# IGresupply.net
KiCad netlist of a schematic drawn in Altium Designer
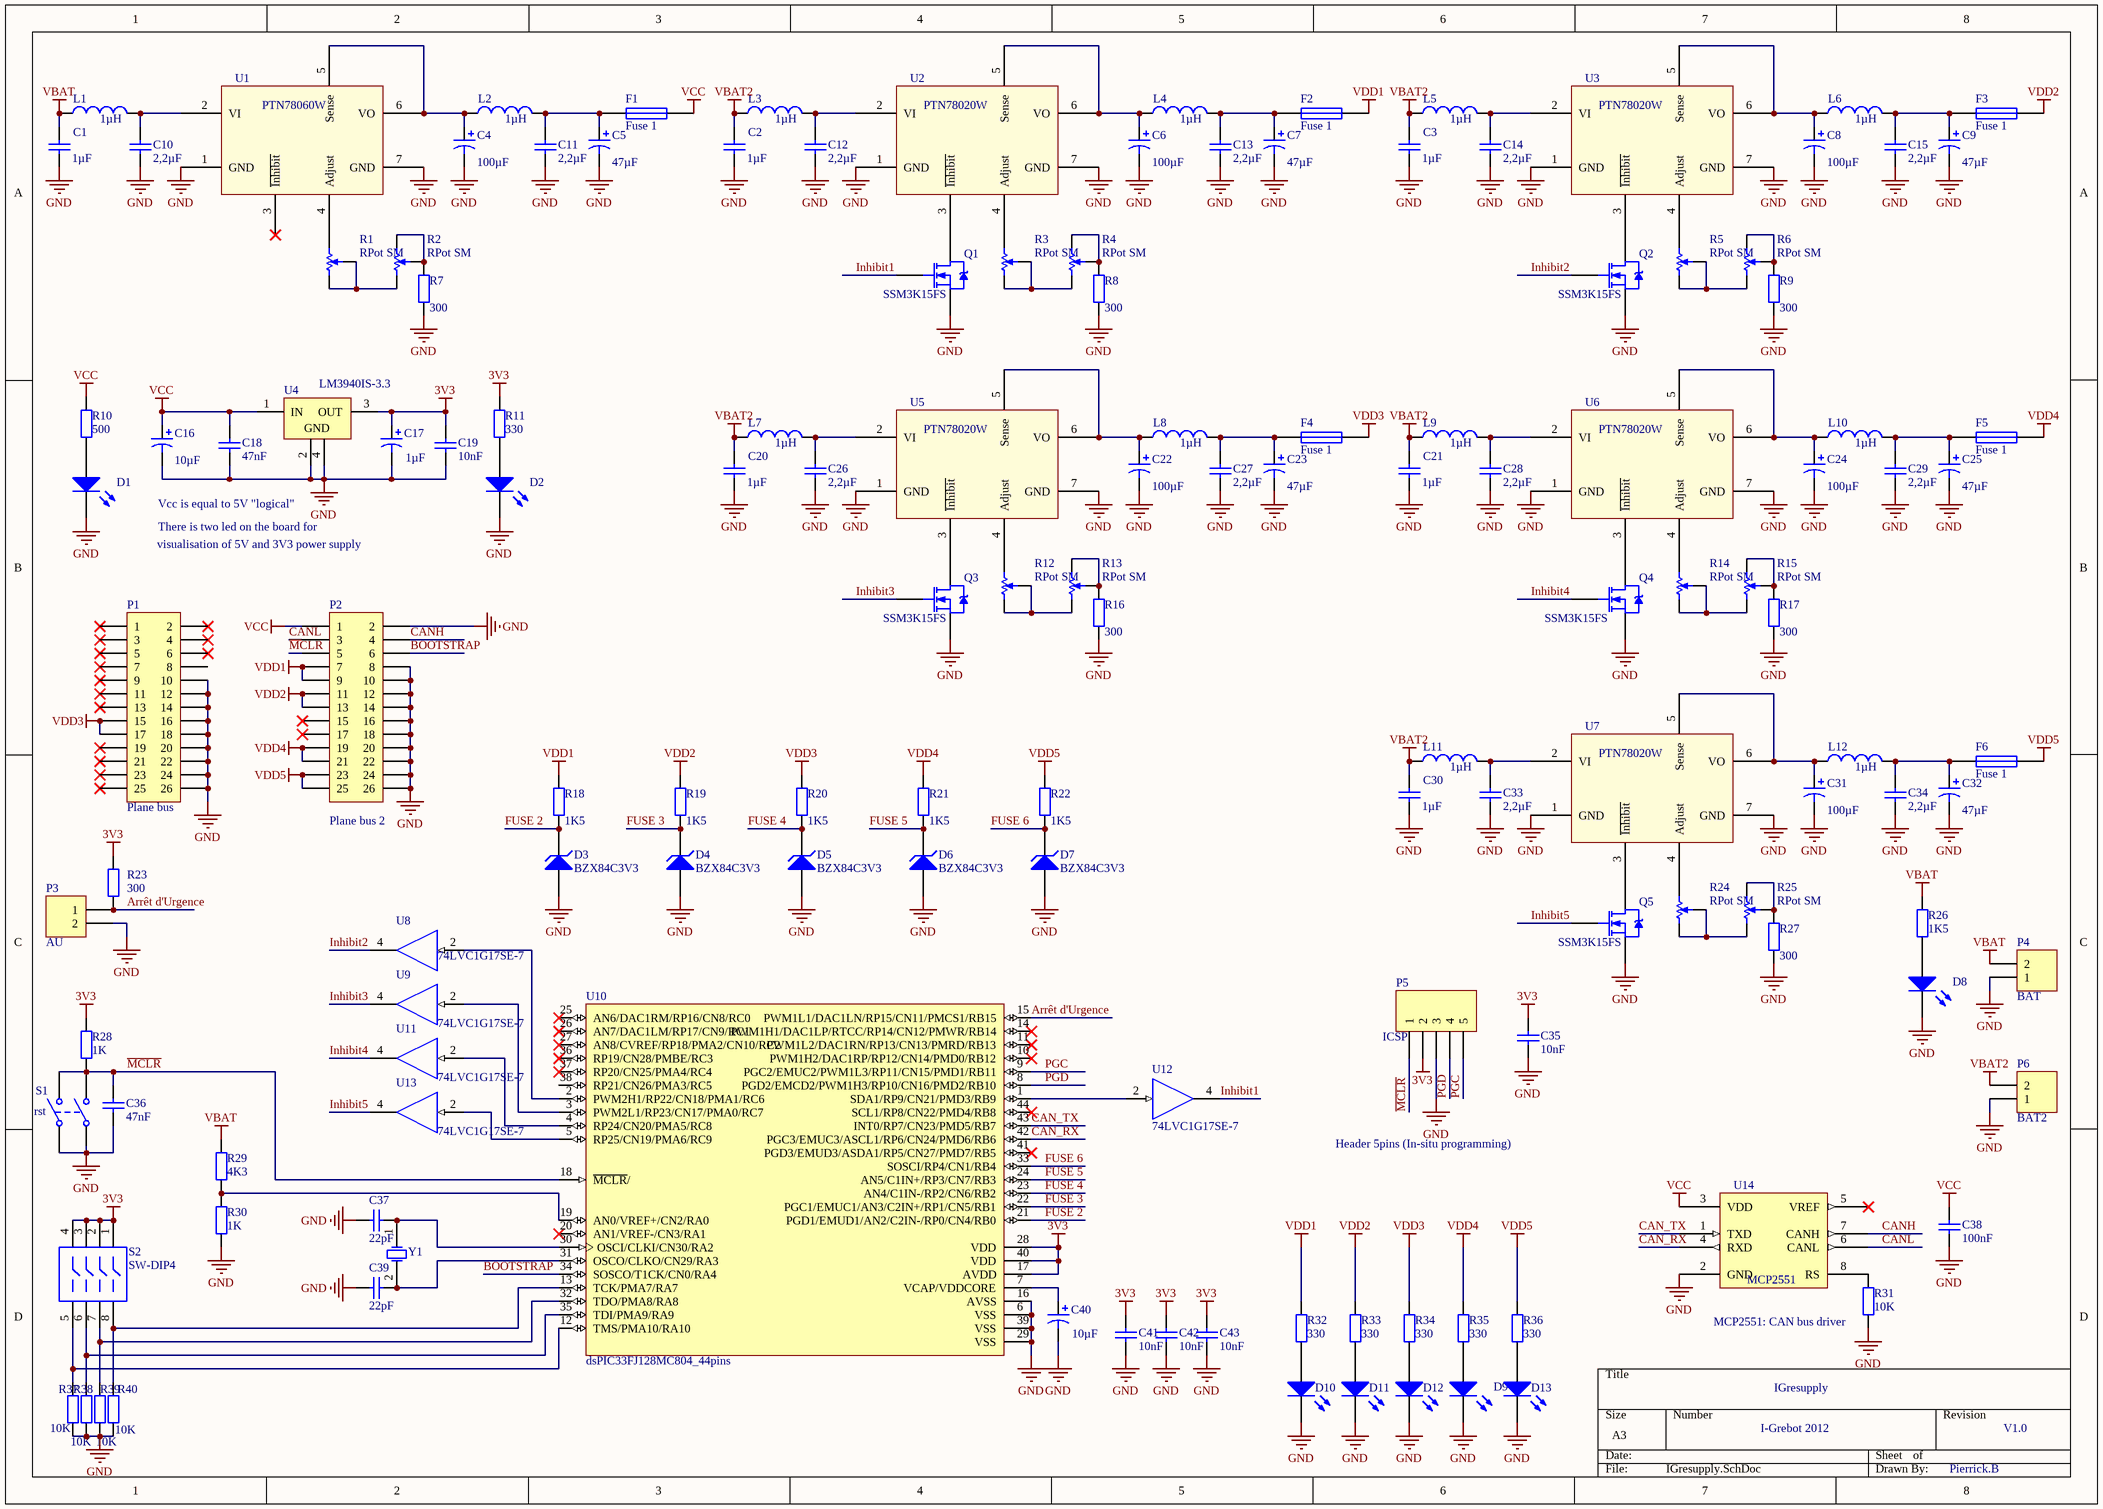
[diagram p0: IGresupply.SchDoc]

(export (version "E")
  (design (tool "Eeschema 10.0.6"))
  (components
    (comp (ref "C1")
      (value "1µF")
      (footprint "Boitier tantale A")
      (description "Capacitor")
      (fields (field (name "Comment") "Cap") (field (name "PUBLISHER") "Altium Limited"))
      (libsource (lib "LIBRARY IGREBOT") (part "Cap"))
    )
    (comp (ref "C2")
      (value "1µF")
      (footprint "Boitier tantale A")
      (description "Capacitor")
      (fields (field (name "Comment") "Cap") (field (name "PUBLISHER") "Altium Limited"))
      (libsource (lib "LIBRARY IGREBOT") (part "Cap"))
    )
    (comp (ref "C3")
      (value "1µF")
      (footprint "Boitier tantale A")
      (description "Capacitor")
      (fields (field (name "Comment") "Cap") (field (name "PUBLISHER") "Altium Limited"))
      (libsource (lib "LIBRARY IGREBOT") (part "Cap"))
    )
    (comp (ref "C4")
      (value "100µF")
      (footprint "Boitier tantale C")
      (description "Polarized Capacitor")
      (fields (field (name "Comment") "Cap Pol") (field (name "PUBLISHER") "Altium Limited"))
      (libsource (lib "LIBRARY IGREBOT") (part "Cap Pol"))
    )
    (comp (ref "C5")
      (value "47µF")
      (footprint "Boitier tantale C")
      (description "Polarized Capacitor")
      (fields (field (name "Comment") "Cap Pol") (field (name "PUBLISHER") "Altium Limited"))
      (libsource (lib "LIBRARY IGREBOT") (part "Cap Pol"))
    )
    (comp (ref "C6")
      (value "100µF")
      (footprint "Boitier tantale C")
      (description "Polarized Capacitor")
      (fields (field (name "Comment") "Cap Pol") (field (name "PUBLISHER") "Altium Limited"))
      (libsource (lib "LIBRARY IGREBOT") (part "Cap Pol"))
    )
    (comp (ref "C7")
      (value "47µF")
      (footprint "Boitier tantale C")
      (description "Polarized Capacitor")
      (fields (field (name "Comment") "Cap Pol") (field (name "PUBLISHER") "Altium Limited"))
      (libsource (lib "LIBRARY IGREBOT") (part "Cap Pol"))
    )
    (comp (ref "C8")
      (value "100µF")
      (footprint "Boitier tantale C")
      (description "Polarized Capacitor")
      (fields (field (name "Comment") "Cap Pol") (field (name "PUBLISHER") "Altium Limited"))
      (libsource (lib "LIBRARY IGREBOT") (part "Cap Pol"))
    )
    (comp (ref "C9")
      (value "47µF")
      (footprint "Boitier tantale C")
      (description "Polarized Capacitor")
      (fields (field (name "Comment") "Cap Pol") (field (name "PUBLISHER") "Altium Limited"))
      (libsource (lib "LIBRARY IGREBOT") (part "Cap Pol"))
    )
    (comp (ref "C10")
      (value "2,2µF")
      (footprint "Boitier tantale A")
      (description "Capacitor")
      (fields (field (name "Comment") "Cap") (field (name "PUBLISHER") "Altium Limited"))
      (libsource (lib "LIBRARY IGREBOT") (part "Cap"))
    )
    (comp (ref "C11")
      (value "2,2µF")
      (footprint "Boitier tantale A")
      (description "Capacitor")
      (fields (field (name "Comment") "Cap") (field (name "PUBLISHER") "Altium Limited"))
      (libsource (lib "LIBRARY IGREBOT") (part "Cap"))
    )
    (comp (ref "C12")
      (value "2,2µF")
      (footprint "Boitier tantale A")
      (description "Capacitor")
      (fields (field (name "Comment") "Cap") (field (name "PUBLISHER") "Altium Limited"))
      (libsource (lib "LIBRARY IGREBOT") (part "Cap"))
    )
    (comp (ref "C13")
      (value "2,2µF")
      (footprint "Boitier tantale A")
      (description "Capacitor")
      (fields (field (name "Comment") "Cap") (field (name "PUBLISHER") "Altium Limited"))
      (libsource (lib "LIBRARY IGREBOT") (part "Cap"))
    )
    (comp (ref "C14")
      (value "2,2µF")
      (footprint "Boitier tantale A")
      (description "Capacitor")
      (fields (field (name "Comment") "Cap") (field (name "PUBLISHER") "Altium Limited"))
      (libsource (lib "LIBRARY IGREBOT") (part "Cap"))
    )
    (comp (ref "C15")
      (value "2,2µF")
      (footprint "Boitier tantale A")
      (description "Capacitor")
      (fields (field (name "Comment") "Cap") (field (name "PUBLISHER") "Altium Limited"))
      (libsource (lib "LIBRARY IGREBOT") (part "Cap"))
    )
    (comp (ref "C16")
      (value "10µF")
      (footprint "Boitier tantale A")
      (description "Polarized Capacitor")
      (fields (field (name "Comment") "Cap Pol") (field (name "PUBLISHER") "Altium Limited"))
      (libsource (lib "I-GREBOT 2009") (part "Cap Pol"))
    )
    (comp (ref "C17")
      (value "1µF")
      (footprint "Boitier tantale A")
      (description "Polarized Capacitor")
      (fields (field (name "Comment") "Cap Pol") (field (name "PUBLISHER") "Altium Limited"))
      (libsource (lib "*") (part "Cap Pol"))
    )
    (comp (ref "C18")
      (value "47nF")
      (footprint "C0603")
      (description "Capacitor")
      (fields (field (name "Comment") "Cap") (field (name "PUBLISHER") "Altium Limited"))
      (libsource (lib "Miscellaneous Devices") (part "Cap"))
    )
    (comp (ref "C19")
      (value "10nF")
      (footprint "C0603")
      (description "Capacitor")
      (fields (field (name "Comment") "Cap") (field (name "PUBLISHER") "Altium Limited"))
      (libsource (lib "Miscellaneous Devices") (part "Cap"))
    )
    (comp (ref "C20")
      (value "1µF")
      (footprint "Boitier tantale A")
      (description "Capacitor")
      (fields (field (name "Comment") "Cap") (field (name "PUBLISHER") "Altium Limited"))
      (libsource (lib "LIBRARY IGREBOT") (part "Cap"))
    )
    (comp (ref "C21")
      (value "1µF")
      (footprint "Boitier tantale A")
      (description "Capacitor")
      (fields (field (name "Comment") "Cap") (field (name "PUBLISHER") "Altium Limited"))
      (libsource (lib "LIBRARY IGREBOT") (part "Cap"))
    )
    (comp (ref "C22")
      (value "100µF")
      (footprint "Boitier tantale C")
      (description "Polarized Capacitor")
      (fields (field (name "Comment") "Cap Pol") (field (name "PUBLISHER") "Altium Limited"))
      (libsource (lib "LIBRARY IGREBOT") (part "Cap Pol"))
    )
    (comp (ref "C23")
      (value "47µF")
      (footprint "Boitier tantale C")
      (description "Polarized Capacitor")
      (fields (field (name "Comment") "Cap Pol") (field (name "PUBLISHER") "Altium Limited"))
      (libsource (lib "LIBRARY IGREBOT") (part "Cap Pol"))
    )
    (comp (ref "C24")
      (value "100µF")
      (footprint "Boitier tantale C")
      (description "Polarized Capacitor")
      (fields (field (name "Comment") "Cap Pol") (field (name "PUBLISHER") "Altium Limited"))
      (libsource (lib "LIBRARY IGREBOT") (part "Cap Pol"))
    )
    (comp (ref "C25")
      (value "47µF")
      (footprint "Boitier tantale C")
      (description "Polarized Capacitor")
      (fields (field (name "Comment") "Cap Pol") (field (name "PUBLISHER") "Altium Limited"))
      (libsource (lib "LIBRARY IGREBOT") (part "Cap Pol"))
    )
    (comp (ref "C26")
      (value "2,2µF")
      (footprint "Boitier tantale A")
      (description "Capacitor")
      (fields (field (name "Comment") "Cap") (field (name "PUBLISHER") "Altium Limited"))
      (libsource (lib "LIBRARY IGREBOT") (part "Cap"))
    )
    (comp (ref "C27")
      (value "2,2µF")
      (footprint "Boitier tantale A")
      (description "Capacitor")
      (fields (field (name "Comment") "Cap") (field (name "PUBLISHER") "Altium Limited"))
      (libsource (lib "LIBRARY IGREBOT") (part "Cap"))
    )
    (comp (ref "C28")
      (value "2,2µF")
      (footprint "Boitier tantale A")
      (description "Capacitor")
      (fields (field (name "Comment") "Cap") (field (name "PUBLISHER") "Altium Limited"))
      (libsource (lib "LIBRARY IGREBOT") (part "Cap"))
    )
    (comp (ref "C29")
      (value "2,2µF")
      (footprint "Boitier tantale A")
      (description "Capacitor")
      (fields (field (name "Comment") "Cap") (field (name "PUBLISHER") "Altium Limited"))
      (libsource (lib "LIBRARY IGREBOT") (part "Cap"))
    )
    (comp (ref "C30")
      (value "1µF")
      (footprint "Boitier tantale A")
      (description "Capacitor")
      (fields (field (name "Comment") "Cap") (field (name "PUBLISHER") "Altium Limited"))
      (libsource (lib "LIBRARY IGREBOT") (part "Cap"))
    )
    (comp (ref "C31")
      (value "100µF")
      (footprint "Boitier tantale C")
      (description "Polarized Capacitor")
      (fields (field (name "Comment") "Cap Pol") (field (name "PUBLISHER") "Altium Limited"))
      (libsource (lib "LIBRARY IGREBOT") (part "Cap Pol"))
    )
    (comp (ref "C32")
      (value "47µF")
      (footprint "Boitier tantale C")
      (description "Polarized Capacitor")
      (fields (field (name "Comment") "Cap Pol") (field (name "PUBLISHER") "Altium Limited"))
      (libsource (lib "LIBRARY IGREBOT") (part "Cap Pol"))
    )
    (comp (ref "C33")
      (value "2,2µF")
      (footprint "Boitier tantale A")
      (description "Capacitor")
      (fields (field (name "Comment") "Cap") (field (name "PUBLISHER") "Altium Limited"))
      (libsource (lib "LIBRARY IGREBOT") (part "Cap"))
    )
    (comp (ref "C34")
      (value "2,2µF")
      (footprint "Boitier tantale A")
      (description "Capacitor")
      (fields (field (name "Comment") "Cap") (field (name "PUBLISHER") "Altium Limited"))
      (libsource (lib "LIBRARY IGREBOT") (part "Cap"))
    )
    (comp (ref "C35")
      (value "10nF")
      (footprint "C0603")
      (description "Capacitor")
      (fields (field (name "Comment") "Cap") (field (name "PUBLISHER") "Altium Limited"))
      (libsource (lib "Miscellaneous Devices") (part "Cap"))
    )
    (comp (ref "C36")
      (value "47nF")
      (footprint "C0603")
      (description "Capacitor")
      (fields (field (name "Comment") "Cap") (field (name "PUBLISHER") "Altium Limited"))
      (libsource (lib "Miscellaneous Devices") (part "Cap"))
    )
    (comp (ref "C37")
      (value "22pF")
      (footprint "C0603")
      (description "Capacitor")
      (fields (field (name "Comment") "Cap") (field (name "PUBLISHER") "Altium Limited"))
      (libsource (lib "Miscellaneous Devices") (part "Cap"))
    )
    (comp (ref "C38")
      (value "100nF")
      (footprint "C0603")
      (description "Capacitor")
      (fields (field (name "Comment") "Cap") (field (name "PUBLISHER") "Altium Limited"))
      (libsource (lib "Miscellaneous Devices") (part "Cap"))
    )
    (comp (ref "C39")
      (value "22pF")
      (footprint "C0603")
      (description "Capacitor")
      (fields (field (name "Comment") "Cap") (field (name "PUBLISHER") "Altium Limited"))
      (libsource (lib "Miscellaneous Devices") (part "Cap"))
    )
    (comp (ref "C40")
      (value "10µF")
      (footprint "Boitier tantale A")
      (description "Polarized Capacitor")
      (fields (field (name "Comment") "Cap Pol") (field (name "PUBLISHER") "Altium Limited"))
      (libsource (lib "*") (part "Cap Pol"))
    )
    (comp (ref "C41")
      (value "10nF")
      (footprint "C0603")
      (description "Capacitor")
      (fields (field (name "Comment") "Cap") (field (name "PUBLISHER") "Altium Limited"))
      (libsource (lib "Miscellaneous Devices") (part "Cap"))
    )
    (comp (ref "C42")
      (value "10nF")
      (footprint "C0603")
      (description "Capacitor")
      (fields (field (name "Comment") "Cap") (field (name "PUBLISHER") "Altium Limited"))
      (libsource (lib "Miscellaneous Devices") (part "Cap"))
    )
    (comp (ref "C43")
      (value "10nF")
      (footprint "C0603")
      (description "Capacitor")
      (fields (field (name "Comment") "Cap") (field (name "PUBLISHER") "Altium Limited"))
      (libsource (lib "Miscellaneous Devices") (part "Cap"))
    )
    (comp (ref "D1")
      (value "LED1")
      (footprint "HSMS-C110")
      (description "Typical RED GaAs LED")
      (fields (field (name "PUBLISHER") "Altium Limited"))
      (libsource (lib "I-GREBOT 2009") (part "LED1"))
    )
    (comp (ref "D2")
      (value "LED1")
      (footprint "HSMS-C110")
      (description "Typical RED GaAs LED")
      (fields (field (name "PUBLISHER") "Altium Limited"))
      (libsource (lib "I-GREBOT 2009") (part "LED1"))
    )
    (comp (ref "D3")
      (value "BZX84C3V3")
      (footprint "SOT-23")
      (description "Zener Diode")
      (fields (field (name "PUBLISHER") "Altium Limited"))
      (libsource (lib "LIBRARY IGREBOT") (part "D Zener"))
    )
    (comp (ref "D4")
      (value "BZX84C3V3")
      (footprint "SOT-23")
      (description "Zener Diode")
      (fields (field (name "PUBLISHER") "Altium Limited"))
      (libsource (lib "LIBRARY IGREBOT") (part "D Zener"))
    )
    (comp (ref "D5")
      (value "BZX84C3V3")
      (footprint "SOT-23")
      (description "Zener Diode")
      (fields (field (name "PUBLISHER") "Altium Limited"))
      (libsource (lib "LIBRARY IGREBOT") (part "D Zener"))
    )
    (comp (ref "D6")
      (value "BZX84C3V3")
      (footprint "SOT-23")
      (description "Zener Diode")
      (fields (field (name "PUBLISHER") "Altium Limited"))
      (libsource (lib "LIBRARY IGREBOT") (part "D Zener"))
    )
    (comp (ref "D7")
      (value "BZX84C3V3")
      (footprint "SOT-23")
      (description "Zener Diode")
      (fields (field (name "PUBLISHER") "Altium Limited"))
      (libsource (lib "LIBRARY IGREBOT") (part "D Zener"))
    )
    (comp (ref "D8")
      (value "LED1")
      (footprint "HSMS-C110")
      (description "Typical RED GaAs LED")
      (fields (field (name "PUBLISHER") "Altium Limited"))
      (libsource (lib "I-GREBOT 2009") (part "LED1"))
    )
    (comp (ref "D9")
      (value "LED1")
      (footprint "HSMS-C110")
      (description "Typical RED GaAs LED")
      (fields (field (name "PUBLISHER") "Altium Limited"))
      (libsource (lib "I-GREBOT 2009") (part "LED1"))
    )
    (comp (ref "D10")
      (value "LED1")
      (footprint "HSMS-C110")
      (description "Typical RED GaAs LED")
      (fields (field (name "PUBLISHER") "Altium Limited"))
      (libsource (lib "I-GREBOT 2009") (part "LED1"))
    )
    (comp (ref "D11")
      (value "LED1")
      (footprint "HSMS-C110")
      (description "Typical RED GaAs LED")
      (fields (field (name "PUBLISHER") "Altium Limited"))
      (libsource (lib "I-GREBOT 2009") (part "LED1"))
    )
    (comp (ref "D12")
      (value "LED1")
      (footprint "HSMS-C110")
      (description "Typical RED GaAs LED")
      (fields (field (name "PUBLISHER") "Altium Limited"))
      (libsource (lib "I-GREBOT 2009") (part "LED1"))
    )
    (comp (ref "D13")
      (value "LED1")
      (footprint "HSMS-C110")
      (description "Typical RED GaAs LED")
      (fields (field (name "PUBLISHER") "Altium Limited"))
      (libsource (lib "I-GREBOT 2009") (part "LED1"))
    )
    (comp (ref "F1")
      (value "Fuse 1")
      (footprint "MCCQ-122")
      (description "Fuse")
      (fields (field (name "PUBLISHER") "Altium Limited"))
      (libsource (lib "LIBRARY IGREBOT") (part "Fuse 1"))
    )
    (comp (ref "F2")
      (value "Fuse 1")
      (footprint "MCCQ-122")
      (description "Fuse")
      (fields (field (name "PUBLISHER") "Altium Limited"))
      (libsource (lib "LIBRARY IGREBOT") (part "Fuse 1"))
    )
    (comp (ref "F3")
      (value "Fuse 1")
      (footprint "MCCQ-122")
      (description "Fuse")
      (fields (field (name "PUBLISHER") "Altium Limited"))
      (libsource (lib "LIBRARY IGREBOT") (part "Fuse 1"))
    )
    (comp (ref "F4")
      (value "Fuse 1")
      (footprint "MCCQ-122")
      (description "Fuse")
      (fields (field (name "PUBLISHER") "Altium Limited"))
      (libsource (lib "LIBRARY IGREBOT") (part "Fuse 1"))
    )
    (comp (ref "F5")
      (value "Fuse 1")
      (footprint "MCCQ-122")
      (description "Fuse")
      (fields (field (name "PUBLISHER") "Altium Limited"))
      (libsource (lib "LIBRARY IGREBOT") (part "Fuse 1"))
    )
    (comp (ref "F6")
      (value "Fuse 1")
      (footprint "MCCQ-122")
      (description "Fuse")
      (fields (field (name "PUBLISHER") "Altium Limited"))
      (libsource (lib "LIBRARY IGREBOT") (part "Fuse 1"))
    )
    (comp (ref "L1")
      (value "1µH")
      (footprint "744772010")
      (description "Inductor")
      (fields (field (name "PUBLISHER") "Altium Limited"))
      (libsource (lib "LIBRARY IGREBOT") (part "Inductor"))
    )
    (comp (ref "L2")
      (value "1µH")
      (footprint "744772010")
      (description "Inductor")
      (fields (field (name "PUBLISHER") "Altium Limited"))
      (libsource (lib "LIBRARY IGREBOT") (part "Inductor"))
    )
    (comp (ref "L3")
      (value "1µH")
      (footprint "744772010")
      (description "Inductor")
      (fields (field (name "PUBLISHER") "Altium Limited"))
      (libsource (lib "LIBRARY IGREBOT") (part "Inductor"))
    )
    (comp (ref "L4")
      (value "1µH")
      (footprint "744772010")
      (description "Inductor")
      (fields (field (name "PUBLISHER") "Altium Limited"))
      (libsource (lib "LIBRARY IGREBOT") (part "Inductor"))
    )
    (comp (ref "L5")
      (value "1µH")
      (footprint "744772010")
      (description "Inductor")
      (fields (field (name "PUBLISHER") "Altium Limited"))
      (libsource (lib "LIBRARY IGREBOT") (part "Inductor"))
    )
    (comp (ref "L6")
      (value "1µH")
      (footprint "744772010")
      (description "Inductor")
      (fields (field (name "PUBLISHER") "Altium Limited"))
      (libsource (lib "LIBRARY IGREBOT") (part "Inductor"))
    )
    (comp (ref "L7")
      (value "1µH")
      (footprint "744772010")
      (description "Inductor")
      (fields (field (name "PUBLISHER") "Altium Limited"))
      (libsource (lib "LIBRARY IGREBOT") (part "Inductor"))
    )
    (comp (ref "L8")
      (value "1µH")
      (footprint "744772010")
      (description "Inductor")
      (fields (field (name "PUBLISHER") "Altium Limited"))
      (libsource (lib "LIBRARY IGREBOT") (part "Inductor"))
    )
    (comp (ref "L9")
      (value "1µH")
      (footprint "744772010")
      (description "Inductor")
      (fields (field (name "PUBLISHER") "Altium Limited"))
      (libsource (lib "LIBRARY IGREBOT") (part "Inductor"))
    )
    (comp (ref "L10")
      (value "1µH")
      (footprint "744772010")
      (description "Inductor")
      (fields (field (name "PUBLISHER") "Altium Limited"))
      (libsource (lib "LIBRARY IGREBOT") (part "Inductor"))
    )
    (comp (ref "L11")
      (value "1µH")
      (footprint "744772010")
      (description "Inductor")
      (fields (field (name "PUBLISHER") "Altium Limited"))
      (libsource (lib "LIBRARY IGREBOT") (part "Inductor"))
    )
    (comp (ref "L12")
      (value "1µH")
      (footprint "744772010")
      (description "Inductor")
      (fields (field (name "PUBLISHER") "Altium Limited"))
      (libsource (lib "LIBRARY IGREBOT") (part "Inductor"))
    )
    (comp (ref "P1")
      (value "Plane bus")
      (footprint "HDR2X13H")
      (description "Header, 13-Pin, Dual row, Right Angle")
      (fields (field (name "PUBLISHER") "Altium Limited"))
      (libsource (lib "Miscellaneous Connectors") (part "Header 13X2H"))
    )
    (comp (ref "P2")
      (value "Plane bus 2")
      (footprint "HDR2X13H")
      (description "Header, 13-Pin, Dual row, Right Angle")
      (fields (field (name "PUBLISHER") "Altium Limited"))
      (libsource (lib "Miscellaneous Connectors") (part "Header 13X2H"))
    )
    (comp (ref "P3")
      (value "AU")
      (footprint "SL 5.08/90")
      (description "Micro-Fit, 3.0")
      (fields (field (name "PUBLISHER") "Altium Limited"))
      (libsource (lib "") (part "0436500203_1"))
    )
    (comp (ref "P4")
      (value "BAT")
      (footprint "SL 5.08/90")
      (description "Micro-Fit, 3.0")
      (fields (field (name "PUBLISHER") "Altium Limited"))
      (libsource (lib "I-GREBOT 2010") (part "0436500203"))
    )
    (comp (ref "P5")
      (value "ICSP")
      (footprint "HDR1X5")
      (description "Header, 5-Pin")
      (fields (field (name "PUBLISHER") "Altium Limited"))
      (libsource (lib "LIBRARY IGREBOT") (part "Header 5"))
    )
    (comp (ref "P6")
      (value "BAT2")
      (footprint "SL 5.08/90")
      (description "Micro-Fit, 3.0")
      (fields (field (name "PUBLISHER") "Altium Limited"))
      (libsource (lib "I-GREBOT 2010") (part "0436500203"))
    )
    (comp (ref "Q1")
      (value "SSM3K15FS")
      (footprint "SOT-23")
      (description "N-Channel Power MOSFET")
      (fields (field (name "PUBLISHER") "Altium Limited"))
      (libsource (lib "LIBRARY IGREBOT") (part "NMOS-2"))
    )
    (comp (ref "Q2")
      (value "SSM3K15FS")
      (footprint "SOT-23")
      (description "N-Channel Power MOSFET")
      (fields (field (name "PUBLISHER") "Altium Limited"))
      (libsource (lib "LIBRARY IGREBOT") (part "NMOS-2"))
    )
    (comp (ref "Q3")
      (value "SSM3K15FS")
      (footprint "SOT-23")
      (description "N-Channel Power MOSFET")
      (fields (field (name "PUBLISHER") "Altium Limited"))
      (libsource (lib "LIBRARY IGREBOT") (part "NMOS-2"))
    )
    (comp (ref "Q4")
      (value "SSM3K15FS")
      (footprint "SOT-23")
      (description "N-Channel Power MOSFET")
      (fields (field (name "PUBLISHER") "Altium Limited"))
      (libsource (lib "LIBRARY IGREBOT") (part "NMOS-2"))
    )
    (comp (ref "Q5")
      (value "SSM3K15FS")
      (footprint "SOT-23")
      (description "N-Channel Power MOSFET")
      (fields (field (name "PUBLISHER") "Altium Limited"))
      (libsource (lib "LIBRARY IGREBOT") (part "NMOS-2"))
    )
    (comp (ref "R1")
      (value "RPot SM")
      (footprint "3296X")
      (description "Square Trimming Potentiometer")
      (fields (field (name "PUBLISHER") "Altium Limited"))
      (libsource (lib "LIBRARY IGREBOT") (part "RPot SM"))
    )
    (comp (ref "R2")
      (value "RPot SM")
      (footprint "3296X")
      (description "Square Trimming Potentiometer")
      (fields (field (name "PUBLISHER") "Altium Limited"))
      (libsource (lib "LIBRARY IGREBOT") (part "RPot SM"))
    )
    (comp (ref "R3")
      (value "RPot SM")
      (footprint "3296X")
      (description "Square Trimming Potentiometer")
      (fields (field (name "PUBLISHER") "Altium Limited"))
      (libsource (lib "LIBRARY IGREBOT") (part "RPot SM"))
    )
    (comp (ref "R4")
      (value "RPot SM")
      (footprint "3296X")
      (description "Square Trimming Potentiometer")
      (fields (field (name "PUBLISHER") "Altium Limited"))
      (libsource (lib "LIBRARY IGREBOT") (part "RPot SM"))
    )
    (comp (ref "R5")
      (value "RPot SM")
      (footprint "3296X")
      (description "Square Trimming Potentiometer")
      (fields (field (name "PUBLISHER") "Altium Limited"))
      (libsource (lib "LIBRARY IGREBOT") (part "RPot SM"))
    )
    (comp (ref "R6")
      (value "RPot SM")
      (footprint "3296X")
      (description "Square Trimming Potentiometer")
      (fields (field (name "PUBLISHER") "Altium Limited"))
      (libsource (lib "LIBRARY IGREBOT") (part "RPot SM"))
    )
    (comp (ref "R7")
      (value "300")
      (footprint "0805")
      (description "Resistor")
      (fields (field (name "Comment") "Res2") (field (name "PUBLISHER") "Altium Limited"))
      (libsource (lib "LIBRARY IGREBOT") (part "Res2"))
    )
    (comp (ref "R8")
      (value "300")
      (footprint "0805")
      (description "Resistor")
      (fields (field (name "Comment") "Res2") (field (name "PUBLISHER") "Altium Limited"))
      (libsource (lib "LIBRARY IGREBOT") (part "Res2"))
    )
    (comp (ref "R9")
      (value "300")
      (footprint "0805")
      (description "Resistor")
      (fields (field (name "Comment") "Res2") (field (name "PUBLISHER") "Altium Limited"))
      (libsource (lib "LIBRARY IGREBOT") (part "Res2"))
    )
    (comp (ref "R10")
      (value "500")
      (footprint "0805")
      (description "Resistor")
      (fields (field (name "Comment") "Res2") (field (name "PUBLISHER") "Altium Limited"))
      (libsource (lib "*") (part "Res2"))
    )
    (comp (ref "R11")
      (value "330")
      (footprint "0805")
      (description "Resistor")
      (fields (field (name "Comment") "Res2") (field (name "PUBLISHER") "Altium Limited"))
      (libsource (lib "*") (part "Res2"))
    )
    (comp (ref "R12")
      (value "RPot SM")
      (footprint "3296X")
      (description "Square Trimming Potentiometer")
      (fields (field (name "PUBLISHER") "Altium Limited"))
      (libsource (lib "LIBRARY IGREBOT") (part "RPot SM"))
    )
    (comp (ref "R13")
      (value "RPot SM")
      (footprint "3296X")
      (description "Square Trimming Potentiometer")
      (fields (field (name "PUBLISHER") "Altium Limited"))
      (libsource (lib "LIBRARY IGREBOT") (part "RPot SM"))
    )
    (comp (ref "R14")
      (value "RPot SM")
      (footprint "3296X")
      (description "Square Trimming Potentiometer")
      (fields (field (name "PUBLISHER") "Altium Limited"))
      (libsource (lib "LIBRARY IGREBOT") (part "RPot SM"))
    )
    (comp (ref "R15")
      (value "RPot SM")
      (footprint "3296X")
      (description "Square Trimming Potentiometer")
      (fields (field (name "PUBLISHER") "Altium Limited"))
      (libsource (lib "LIBRARY IGREBOT") (part "RPot SM"))
    )
    (comp (ref "R16")
      (value "300")
      (footprint "0805")
      (description "Resistor")
      (fields (field (name "Comment") "Res2") (field (name "PUBLISHER") "Altium Limited"))
      (libsource (lib "LIBRARY IGREBOT") (part "Res2"))
    )
    (comp (ref "R17")
      (value "300")
      (footprint "0805")
      (description "Resistor")
      (fields (field (name "Comment") "Res2") (field (name "PUBLISHER") "Altium Limited"))
      (libsource (lib "LIBRARY IGREBOT") (part "Res2"))
    )
    (comp (ref "R18")
      (value "1K5")
      (footprint "0805")
      (description "Resistor")
      (fields (field (name "Comment") "Res2") (field (name "PUBLISHER") "Altium Limited"))
      (libsource (lib "LIBRARY IGREBOT") (part "Res2"))
    )
    (comp (ref "R19")
      (value "1K5")
      (footprint "0805")
      (description "Resistor")
      (fields (field (name "Comment") "Res2") (field (name "PUBLISHER") "Altium Limited"))
      (libsource (lib "LIBRARY IGREBOT") (part "Res2"))
    )
    (comp (ref "R20")
      (value "1K5")
      (footprint "0805")
      (description "Resistor")
      (fields (field (name "Comment") "Res2") (field (name "PUBLISHER") "Altium Limited"))
      (libsource (lib "LIBRARY IGREBOT") (part "Res2"))
    )
    (comp (ref "R21")
      (value "1K5")
      (footprint "0805")
      (description "Resistor")
      (fields (field (name "Comment") "Res2") (field (name "PUBLISHER") "Altium Limited"))
      (libsource (lib "LIBRARY IGREBOT") (part "Res2"))
    )
    (comp (ref "R22")
      (value "1K5")
      (footprint "0805")
      (description "Resistor")
      (fields (field (name "Comment") "Res2") (field (name "PUBLISHER") "Altium Limited"))
      (libsource (lib "LIBRARY IGREBOT") (part "Res2"))
    )
    (comp (ref "R23")
      (value "300")
      (footprint "0805")
      (description "Resistor")
      (fields (field (name "Comment") "Res2") (field (name "PUBLISHER") "Altium Limited"))
      (libsource (lib "LIBRARY IGREBOT") (part "Res2"))
    )
    (comp (ref "R24")
      (value "RPot SM")
      (footprint "3296X")
      (description "Square Trimming Potentiometer")
      (fields (field (name "PUBLISHER") "Altium Limited"))
      (libsource (lib "LIBRARY IGREBOT") (part "RPot SM"))
    )
    (comp (ref "R25")
      (value "RPot SM")
      (footprint "3296X")
      (description "Square Trimming Potentiometer")
      (fields (field (name "PUBLISHER") "Altium Limited"))
      (libsource (lib "LIBRARY IGREBOT") (part "RPot SM"))
    )
    (comp (ref "R26")
      (value "1K5")
      (footprint "0805")
      (description "Resistor")
      (fields (field (name "Comment") "Res2") (field (name "PUBLISHER") "Altium Limited"))
      (libsource (lib "*") (part "Res2"))
    )
    (comp (ref "R27")
      (value "300")
      (footprint "0805")
      (description "Resistor")
      (fields (field (name "Comment") "Res2") (field (name "PUBLISHER") "Altium Limited"))
      (libsource (lib "LIBRARY IGREBOT") (part "Res2"))
    )
    (comp (ref "R28")
      (value "1K")
      (footprint "0805")
      (description "Resistor")
      (fields (field (name "Comment") "Res2") (field (name "PUBLISHER") "Altium Limited"))
      (libsource (lib "*") (part "Res2"))
    )
    (comp (ref "R29")
      (value "4K3")
      (footprint "0805")
      (description "Resistor")
      (fields (field (name "Comment") "Res2") (field (name "PUBLISHER") "Altium Limited"))
      (libsource (lib "*") (part "Res2"))
    )
    (comp (ref "R30")
      (value "1K")
      (footprint "0805")
      (description "Resistor")
      (fields (field (name "Comment") "Res2") (field (name "PUBLISHER") "Altium Limited"))
      (libsource (lib "*") (part "Res2"))
    )
    (comp (ref "R31")
      (value "10K")
      (footprint "0805")
      (description "Resistor")
      (fields (field (name "Comment") "Res2") (field (name "PUBLISHER") "Altium Limited"))
      (libsource (lib "") (part "Res2_1"))
    )
    (comp (ref "R32")
      (value "330")
      (footprint "0805")
      (description "Resistor")
      (fields (field (name "Comment") "Res2") (field (name "PUBLISHER") "Altium Limited"))
      (libsource (lib "*") (part "Res2"))
    )
    (comp (ref "R33")
      (value "330")
      (footprint "0805")
      (description "Resistor")
      (fields (field (name "Comment") "Res2") (field (name "PUBLISHER") "Altium Limited"))
      (libsource (lib "*") (part "Res2"))
    )
    (comp (ref "R34")
      (value "330")
      (footprint "0805")
      (description "Resistor")
      (fields (field (name "Comment") "Res2") (field (name "PUBLISHER") "Altium Limited"))
      (libsource (lib "*") (part "Res2"))
    )
    (comp (ref "R35")
      (value "330")
      (footprint "0805")
      (description "Resistor")
      (fields (field (name "Comment") "Res2") (field (name "PUBLISHER") "Altium Limited"))
      (libsource (lib "*") (part "Res2"))
    )
    (comp (ref "R36")
      (value "330")
      (footprint "0805")
      (description "Resistor")
      (fields (field (name "Comment") "Res2") (field (name "PUBLISHER") "Altium Limited"))
      (libsource (lib "*") (part "Res2"))
    )
    (comp (ref "R37")
      (value "10K")
      (footprint "0603")
      (description "Resistor")
      (fields (field (name "Comment") "Res2") (field (name "PUBLISHER") "Altium Limited"))
      (libsource (lib "*") (part "Res2"))
    )
    (comp (ref "R38")
      (value "10K")
      (footprint "0603")
      (description "Resistor")
      (fields (field (name "Comment") "Res2") (field (name "PUBLISHER") "Altium Limited"))
      (libsource (lib "*") (part "Res2"))
    )
    (comp (ref "R39")
      (value "10K")
      (footprint "0603")
      (description "Resistor")
      (fields (field (name "Comment") "Res2") (field (name "PUBLISHER") "Altium Limited"))
      (libsource (lib "*") (part "Res2"))
    )
    (comp (ref "R40")
      (value "10K")
      (footprint "0603")
      (description "Resistor")
      (fields (field (name "Comment") "Res2") (field (name "PUBLISHER") "Altium Limited"))
      (libsource (lib "*") (part "Res2"))
    )
    (comp (ref "S1")
      (value "rst")
      (footprint "Bouton poussoir")
      (description "Double-Pole, Single-Throw Switch")
      (fields (field (name "PUBLISHER") "Altium Limited"))
      (libsource (lib "*") (part "SW-DPST"))
    )
    (comp (ref "S2")
      (value "SW-DIP4")
      (footprint "DIP-8")
      (description "DIP Switch")
      (fields (field (name "PUBLISHER") "Altium Limited"))
      (libsource (lib "Miscellaneous Devices") (part "SW-DIP4"))
    )
    (comp (ref "U1")
      (value "PTN78060W")
      (footprint "EUW")
      (libsource (lib "LIBRARY IGREBOT") (part "PTN78060W"))
    )
    (comp (ref "U2")
      (value "PTN78020W")
      (footprint "EUK")
      (libsource (lib "LIBRARY IGREBOT") (part "PTN78020W"))
    )
    (comp (ref "U3")
      (value "PTN78020W")
      (footprint "EUK")
      (libsource (lib "LIBRARY IGREBOT") (part "PTN78020W"))
    )
    (comp (ref "U4")
      (value "LM3940IS-3.3")
      (footprint "SOT223")
      (description "1A Low-Dropout Regulator For 5V to 3.3V Conversion")
      (fields (field (name "PUBLISHER") "Altium Limited"))
      (libsource (lib "I-GREBOT 2009") (part "LM3940IS-3.3"))
    )
    (comp (ref "U5")
      (value "PTN78020W")
      (footprint "EUK")
      (libsource (lib "LIBRARY IGREBOT") (part "PTN78020W"))
    )
    (comp (ref "U6")
      (value "PTN78020W")
      (footprint "EUK")
      (libsource (lib "LIBRARY IGREBOT") (part "PTN78020W"))
    )
    (comp (ref "U7")
      (value "PTN78020W")
      (footprint "EUK")
      (libsource (lib "LIBRARY IGREBOT") (part "PTN78020W"))
    )
    (comp (ref "U8")
      (value "74LVC1G17SE-7")
      (footprint "DBV")
      (description "SINGLE BUS BUFFER GATE  WITH 3-STATE OUTPUT")
      (fields (field (name "PUBLISHER") "Altium Limited"))
      (libsource (lib "LIBRARY IGREBOT") (part "74LVC1G17SE-7"))
    )
    (comp (ref "U9")
      (value "74LVC1G17SE-7")
      (footprint "DBV")
      (description "SINGLE BUS BUFFER GATE  WITH 3-STATE OUTPUT")
      (fields (field (name "PUBLISHER") "Altium Limited"))
      (libsource (lib "LIBRARY IGREBOT") (part "74LVC1G17SE-7"))
    )
    (comp (ref "U10")
      (value "dsPIC33FJ128MC804_44pins")
      (footprint "TQFP-44")
      (libsource (lib "I-GREBOT 2009") (part "dsPIC33FJ128MC804_44pins"))
    )
    (comp (ref "U11")
      (value "74LVC1G17SE-7")
      (footprint "DBV")
      (description "SINGLE BUS BUFFER GATE  WITH 3-STATE OUTPUT")
      (fields (field (name "PUBLISHER") "Altium Limited"))
      (libsource (lib "LIBRARY IGREBOT") (part "74LVC1G17SE-7"))
    )
    (comp (ref "U12")
      (value "74LVC1G17SE-7")
      (footprint "DBV")
      (description "SINGLE BUS BUFFER GATE  WITH 3-STATE OUTPUT")
      (fields (field (name "PUBLISHER") "Altium Limited"))
      (libsource (lib "LIBRARY IGREBOT") (part "74LVC1G17SE-7"))
    )
    (comp (ref "U13")
      (value "74LVC1G17SE-7")
      (footprint "DBV")
      (description "SINGLE BUS BUFFER GATE  WITH 3-STATE OUTPUT")
      (fields (field (name "PUBLISHER") "Altium Limited"))
      (libsource (lib "LIBRARY IGREBOT") (part "74LVC1G17SE-7"))
    )
    (comp (ref "U14")
      (value "MCP2551")
      (footprint "SOIC150-8")
      (description "High Speed Can Transceiver")
      (fields (field (name "PUBLISHER") "Altium Limited"))
      (libsource (lib "*") (part "MCP2551"))
    )
    (comp (ref "Y1")
      (value "XTAL")
      (footprint "HC49US")
      (description "Crystal Oscillator")
      (fields (field (name "PUBLISHER") "Altium Limited"))
      (libsource (lib "*") (part "XTAL"))
    )
  )
  (nets
    (net (code "1") (name "/Arrêt d'Urgence") (class "Default")
      (node (ref "P3") (pin "1") (pinfunction "1_1") (pintype "passive"))
      (node (ref "R23") (pin "1") (pinfunction "1_1") (pintype "passive"))
      (node (ref "U10") (pin "15") (pinfunction "PWM1L1/DAC1LN/RP15/CN11/PMCS1/RB15_15") (pintype "bidirectional"))
    )
    (net (code "2") (name "/BOOTSTRAP") (class "Default")
      (node (ref "P2") (pin "6") (pinfunction "6_6") (pintype "passive"))
      (node (ref "U10") (pin "34") (pinfunction "SOSCO/T1CK/CN0/RA4_34") (pintype "bidirectional"))
    )
    (net (code "3") (name "/CANH") (class "Default")
      (node (ref "P2") (pin "4") (pinfunction "4_4") (pintype "passive"))
      (node (ref "U14") (pin "7") (pinfunction "CANH_7") (pintype "output"))
    )
    (net (code "4") (name "/CANL") (class "Default")
      (node (ref "P2") (pin "3") (pinfunction "3_3") (pintype "passive"))
      (node (ref "U14") (pin "6") (pinfunction "CANL_6") (pintype "output"))
    )
    (net (code "5") (name "/CAN_RX") (class "Default")
      (node (ref "U10") (pin "42") (pinfunction "PGC3/EMUC3/ASCL1/RP6/CN24/PMD6/RB6_42") (pintype "bidirectional"))
      (node (ref "U14") (pin "4") (pinfunction "RXD_4") (pintype "output"))
    )
    (net (code "6") (name "/CAN_TX") (class "Default")
      (node (ref "U10") (pin "43") (pinfunction "INT0/RP7/CN23/PMD5/RB7_43") (pintype "bidirectional"))
      (node (ref "U14") (pin "1") (pinfunction "TXD_1") (pintype "input"))
    )
    (net (code "7") (name "/FUSE 2") (class "Default")
      (node (ref "D3") (pin "3") (pinfunction "K_3") (pintype "passive"))
      (node (ref "R18") (pin "1") (pinfunction "1_1") (pintype "passive"))
      (node (ref "U10") (pin "21") (pinfunction "PGD1/EMUD1/AN2/C2IN-/RP0/CN4/RB0_21") (pintype "bidirectional"))
    )
    (net (code "8") (name "/FUSE 3") (class "Default")
      (node (ref "D4") (pin "3") (pinfunction "K_3") (pintype "passive"))
      (node (ref "R19") (pin "1") (pinfunction "1_1") (pintype "passive"))
      (node (ref "U10") (pin "22") (pinfunction "PGC1/EMUC1/AN3/C2IN+/RP1/CN5/RB1_22") (pintype "bidirectional"))
    )
    (net (code "9") (name "/FUSE 4") (class "Default")
      (node (ref "D5") (pin "3") (pinfunction "K_3") (pintype "passive"))
      (node (ref "R20") (pin "1") (pinfunction "1_1") (pintype "passive"))
      (node (ref "U10") (pin "23") (pinfunction "AN4/C1IN-/RP2/CN6/RB2_23") (pintype "bidirectional"))
    )
    (net (code "10") (name "/FUSE 5") (class "Default")
      (node (ref "D6") (pin "3") (pinfunction "K_3") (pintype "passive"))
      (node (ref "R21") (pin "1") (pinfunction "1_1") (pintype "passive"))
      (node (ref "U10") (pin "24") (pinfunction "AN5/C1IN+/RP3/CN7/RB3_24") (pintype "bidirectional"))
    )
    (net (code "11") (name "/FUSE 6") (class "Default")
      (node (ref "D7") (pin "3") (pinfunction "K_3") (pintype "passive"))
      (node (ref "R22") (pin "1") (pinfunction "1_1") (pintype "passive"))
      (node (ref "U10") (pin "33") (pinfunction "SOSCI/RP4/CN1/RB4_33") (pintype "bidirectional"))
    )
    (net (code "12") (name "/Inhibit1") (class "Default")
      (node (ref "Q1") (pin "1") (pinfunction "G_1") (pintype "passive"))
      (node (ref "U12") (pin "4") (pinfunction "Y_4") (pintype "tri_state"))
    )
    (net (code "13") (name "/Inhibit2") (class "Default")
      (node (ref "Q2") (pin "1") (pinfunction "G_1") (pintype "passive"))
      (node (ref "U8") (pin "4") (pinfunction "Y_4") (pintype "tri_state"))
    )
    (net (code "14") (name "/Inhibit3") (class "Default")
      (node (ref "Q3") (pin "1") (pinfunction "G_1") (pintype "passive"))
      (node (ref "U9") (pin "4") (pinfunction "Y_4") (pintype "tri_state"))
    )
    (net (code "15") (name "/Inhibit4") (class "Default")
      (node (ref "Q4") (pin "1") (pinfunction "G_1") (pintype "passive"))
      (node (ref "U11") (pin "4") (pinfunction "Y_4") (pintype "tri_state"))
    )
    (net (code "16") (name "/Inhibit5") (class "Default")
      (node (ref "Q5") (pin "1") (pinfunction "G_1") (pintype "passive"))
      (node (ref "U13") (pin "4") (pinfunction "Y_4") (pintype "tri_state"))
    )
    (net (code "17") (name "/PGC") (class "Default")
      (node (ref "P5") (pin "5") (pinfunction "5_5") (pintype "passive"))
      (node (ref "U10") (pin "9") (pinfunction "PGC2/EMUC2/PWM1L3/RP11/CN15/PMD1/RB11_9") (pintype "bidirectional"))
    )
    (net (code "18") (name "/PGD") (class "Default")
      (node (ref "P5") (pin "4") (pinfunction "4_4") (pintype "passive"))
      (node (ref "U10") (pin "8") (pinfunction "PGD2/EMCD2/PWM1H3/RP10/CN16/PMD2/RB10_8") (pintype "bidirectional"))
    )
    (net (code "19") (name "/~{MCLR}") (class "Default")
      (node (ref "C36") (pin "2") (pinfunction "2_2") (pintype "passive"))
      (node (ref "P2") (pin "5") (pinfunction "5_5") (pintype "passive"))
      (node (ref "P5") (pin "1") (pinfunction "1_1") (pintype "passive"))
      (node (ref "R28") (pin "1") (pinfunction "1_1") (pintype "passive"))
      (node (ref "S1") (pin "2") (pinfunction "NO1_2") (pintype "passive"))
      (node (ref "S1") (pin "4") (pinfunction "NO2_4") (pintype "passive"))
      (node (ref "U10") (pin "18") (pinfunction "~{MCLR}/_18") (pintype "input"))
    )
    (net (code "20") (name "3V3") (class "Default")
      (node (ref "C17") (pin "1") (pinfunction "1_1") (pintype "passive"))
      (node (ref "C19") (pin "2") (pinfunction "2_2") (pintype "passive"))
      (node (ref "C35") (pin "2") (pinfunction "2_2") (pintype "passive"))
      (node (ref "C41") (pin "2") (pinfunction "2_2") (pintype "passive"))
      (node (ref "C42") (pin "2") (pinfunction "2_2") (pintype "passive"))
      (node (ref "C43") (pin "2") (pinfunction "2_2") (pintype "passive"))
      (node (ref "P5") (pin "2") (pinfunction "2_2") (pintype "passive"))
      (node (ref "R11") (pin "2") (pinfunction "2_2") (pintype "passive"))
      (node (ref "R23") (pin "2") (pinfunction "2_2") (pintype "passive"))
      (node (ref "R28") (pin "2") (pinfunction "2_2") (pintype "passive"))
      (node (ref "S2") (pin "1") (pinfunction "1_1") (pintype "passive"))
      (node (ref "S2") (pin "2") (pinfunction "2_2") (pintype "passive"))
      (node (ref "S2") (pin "3") (pinfunction "3_3") (pintype "passive"))
      (node (ref "S2") (pin "4") (pinfunction "4_4") (pintype "passive"))
      (node (ref "U10") (pin "17") (pinfunction "AVDD_17") (pintype "power_in"))
      (node (ref "U10") (pin "28") (pinfunction "VDD_28") (pintype "power_in"))
      (node (ref "U10") (pin "40") (pinfunction "VDD_40") (pintype "power_in"))
      (node (ref "U4") (pin "3") (pinfunction "OUT_3") (pintype "power_in"))
    )
    (net (code "21") (name "GND") (class "Default")
      (node (ref "C1") (pin "1") (pinfunction "1_1") (pintype "passive"))
      (node (ref "C10") (pin "1") (pinfunction "1_1") (pintype "passive"))
      (node (ref "C11") (pin "1") (pinfunction "1_1") (pintype "passive"))
      (node (ref "C12") (pin "1") (pinfunction "1_1") (pintype "passive"))
      (node (ref "C13") (pin "1") (pinfunction "1_1") (pintype "passive"))
      (node (ref "C14") (pin "1") (pinfunction "1_1") (pintype "passive"))
      (node (ref "C15") (pin "1") (pinfunction "1_1") (pintype "passive"))
      (node (ref "C16") (pin "2") (pinfunction "2_2") (pintype "passive"))
      (node (ref "C17") (pin "2") (pinfunction "2_2") (pintype "passive"))
      (node (ref "C18") (pin "1") (pinfunction "1_1") (pintype "passive"))
      (node (ref "C19") (pin "1") (pinfunction "1_1") (pintype "passive"))
      (node (ref "C2") (pin "1") (pinfunction "1_1") (pintype "passive"))
      (node (ref "C20") (pin "1") (pinfunction "1_1") (pintype "passive"))
      (node (ref "C21") (pin "1") (pinfunction "1_1") (pintype "passive"))
      (node (ref "C22") (pin "2") (pinfunction "2_2") (pintype "passive"))
      (node (ref "C23") (pin "2") (pinfunction "2_2") (pintype "passive"))
      (node (ref "C24") (pin "2") (pinfunction "2_2") (pintype "passive"))
      (node (ref "C25") (pin "2") (pinfunction "2_2") (pintype "passive"))
      (node (ref "C26") (pin "1") (pinfunction "1_1") (pintype "passive"))
      (node (ref "C27") (pin "1") (pinfunction "1_1") (pintype "passive"))
      (node (ref "C28") (pin "1") (pinfunction "1_1") (pintype "passive"))
      (node (ref "C29") (pin "1") (pinfunction "1_1") (pintype "passive"))
      (node (ref "C3") (pin "1") (pinfunction "1_1") (pintype "passive"))
      (node (ref "C30") (pin "1") (pinfunction "1_1") (pintype "passive"))
      (node (ref "C31") (pin "2") (pinfunction "2_2") (pintype "passive"))
      (node (ref "C32") (pin "2") (pinfunction "2_2") (pintype "passive"))
      (node (ref "C33") (pin "1") (pinfunction "1_1") (pintype "passive"))
      (node (ref "C34") (pin "1") (pinfunction "1_1") (pintype "passive"))
      (node (ref "C35") (pin "1") (pinfunction "1_1") (pintype "passive"))
      (node (ref "C36") (pin "1") (pinfunction "1_1") (pintype "passive"))
      (node (ref "C37") (pin "1") (pinfunction "1_1") (pintype "passive"))
      (node (ref "C38") (pin "1") (pinfunction "1_1") (pintype "passive"))
      (node (ref "C39") (pin "1") (pinfunction "1_1") (pintype "passive"))
      (node (ref "C4") (pin "2") (pinfunction "2_2") (pintype "passive"))
      (node (ref "C40") (pin "2") (pinfunction "2_2") (pintype "passive"))
      (node (ref "C41") (pin "1") (pinfunction "1_1") (pintype "passive"))
      (node (ref "C42") (pin "1") (pinfunction "1_1") (pintype "passive"))
      (node (ref "C43") (pin "1") (pinfunction "1_1") (pintype "passive"))
      (node (ref "C5") (pin "2") (pinfunction "2_2") (pintype "passive"))
      (node (ref "C6") (pin "2") (pinfunction "2_2") (pintype "passive"))
      (node (ref "C7") (pin "2") (pinfunction "2_2") (pintype "passive"))
      (node (ref "C8") (pin "2") (pinfunction "2_2") (pintype "passive"))
      (node (ref "C9") (pin "2") (pinfunction "2_2") (pintype "passive"))
      (node (ref "D1") (pin "2") (pinfunction "K_2") (pintype "passive"))
      (node (ref "D10") (pin "2") (pinfunction "K_2") (pintype "passive"))
      (node (ref "D11") (pin "2") (pinfunction "K_2") (pintype "passive"))
      (node (ref "D12") (pin "2") (pinfunction "K_2") (pintype "passive"))
      (node (ref "D13") (pin "2") (pinfunction "K_2") (pintype "passive"))
      (node (ref "D2") (pin "2") (pinfunction "K_2") (pintype "passive"))
      (node (ref "D3") (pin "1") (pinfunction "A_1") (pintype "passive"))
      (node (ref "D4") (pin "1") (pinfunction "A_1") (pintype "passive"))
      (node (ref "D5") (pin "1") (pinfunction "A_1") (pintype "passive"))
      (node (ref "D6") (pin "1") (pinfunction "A_1") (pintype "passive"))
      (node (ref "D7") (pin "1") (pinfunction "A_1") (pintype "passive"))
      (node (ref "D8") (pin "2") (pinfunction "K_2") (pintype "passive"))
      (node (ref "D9") (pin "2") (pinfunction "K_2") (pintype "passive"))
      (node (ref "P1") (pin "10") (pinfunction "10_10") (pintype "passive"))
      (node (ref "P1") (pin "12") (pinfunction "12_12") (pintype "passive"))
      (node (ref "P1") (pin "14") (pinfunction "14_14") (pintype "passive"))
      (node (ref "P1") (pin "16") (pinfunction "16_16") (pintype "passive"))
      (node (ref "P1") (pin "18") (pinfunction "18_18") (pintype "passive"))
      (node (ref "P1") (pin "20") (pinfunction "20_20") (pintype "passive"))
      (node (ref "P1") (pin "22") (pinfunction "22_22") (pintype "passive"))
      (node (ref "P1") (pin "24") (pinfunction "24_24") (pintype "passive"))
      (node (ref "P1") (pin "26") (pinfunction "26_26") (pintype "passive"))
      (node (ref "P2") (pin "10") (pinfunction "10_10") (pintype "passive"))
      (node (ref "P2") (pin "12") (pinfunction "12_12") (pintype "passive"))
      (node (ref "P2") (pin "14") (pinfunction "14_14") (pintype "passive"))
      (node (ref "P2") (pin "16") (pinfunction "16_16") (pintype "passive"))
      (node (ref "P2") (pin "18") (pinfunction "18_18") (pintype "passive"))
      (node (ref "P2") (pin "2") (pinfunction "2_2") (pintype "passive"))
      (node (ref "P2") (pin "20") (pinfunction "20_20") (pintype "passive"))
      (node (ref "P2") (pin "22") (pinfunction "22_22") (pintype "passive"))
      (node (ref "P2") (pin "24") (pinfunction "24_24") (pintype "passive"))
      (node (ref "P2") (pin "26") (pinfunction "26_26") (pintype "passive"))
      (node (ref "P2") (pin "8") (pinfunction "8_8") (pintype "passive"))
      (node (ref "P3") (pin "2") (pinfunction "2_2") (pintype "passive"))
      (node (ref "P4") (pin "1") (pinfunction "1_1") (pintype "passive"))
      (node (ref "P5") (pin "3") (pinfunction "3_3") (pintype "passive"))
      (node (ref "P6") (pin "1") (pinfunction "1_1") (pintype "passive"))
      (node (ref "Q1") (pin "3") (pinfunction "S_3") (pintype "passive"))
      (node (ref "Q2") (pin "3") (pinfunction "S_3") (pintype "passive"))
      (node (ref "Q3") (pin "3") (pinfunction "S_3") (pintype "passive"))
      (node (ref "Q4") (pin "3") (pinfunction "S_3") (pintype "passive"))
      (node (ref "Q5") (pin "3") (pinfunction "S_3") (pintype "passive"))
      (node (ref "R16") (pin "1") (pinfunction "1_1") (pintype "passive"))
      (node (ref "R17") (pin "1") (pinfunction "1_1") (pintype "passive"))
      (node (ref "R27") (pin "1") (pinfunction "1_1") (pintype "passive"))
      (node (ref "R30") (pin "1") (pinfunction "1_1") (pintype "passive"))
      (node (ref "R31") (pin "1") (pinfunction "1_1") (pintype "passive"))
      (node (ref "R37") (pin "1") (pinfunction "1_1") (pintype "passive"))
      (node (ref "R38") (pin "1") (pinfunction "1_1") (pintype "passive"))
      (node (ref "R39") (pin "1") (pinfunction "1_1") (pintype "passive"))
      (node (ref "R40") (pin "1") (pinfunction "1_1") (pintype "passive"))
      (node (ref "R7") (pin "1") (pinfunction "1_1") (pintype "passive"))
      (node (ref "R8") (pin "1") (pinfunction "1_1") (pintype "passive"))
      (node (ref "R9") (pin "1") (pinfunction "1_1") (pintype "passive"))
      (node (ref "S1") (pin "1") (pinfunction "COMMON1_1") (pintype "passive"))
      (node (ref "S1") (pin "3") (pinfunction "COMMON2_3") (pintype "passive"))
      (node (ref "U1") (pin "1") (pinfunction "GND_1") (pintype "power_in"))
      (node (ref "U1") (pin "7") (pinfunction "GND_7") (pintype "power_in"))
      (node (ref "U10") (pin "16") (pinfunction "AVSS_16") (pintype "power_in"))
      (node (ref "U10") (pin "29") (pinfunction "VSS_29") (pintype "power_in"))
      (node (ref "U10") (pin "39") (pinfunction "VSS_39") (pintype "power_in"))
      (node (ref "U10") (pin "6") (pinfunction "VSS_6") (pintype "power_in"))
      (node (ref "U11") (pin "3") (pinfunction "GND_3") (pintype "power_in"))
      (node (ref "U12") (pin "3") (pinfunction "GND_3") (pintype "power_in"))
      (node (ref "U13") (pin "3") (pinfunction "GND_3") (pintype "power_in"))
      (node (ref "U14") (pin "2") (pinfunction "GND_2") (pintype "power_in"))
      (node (ref "U2") (pin "1") (pinfunction "GND_1") (pintype "power_in"))
      (node (ref "U2") (pin "7") (pinfunction "GND_7") (pintype "power_in"))
      (node (ref "U3") (pin "1") (pinfunction "GND_1") (pintype "power_in"))
      (node (ref "U3") (pin "7") (pinfunction "GND_7") (pintype "power_in"))
      (node (ref "U4") (pin "2") (pinfunction "GND_2") (pintype "power_in"))
      (node (ref "U4") (pin "4") (pinfunction "GND_4") (pintype "power_in"))
      (node (ref "U5") (pin "1") (pinfunction "GND_1") (pintype "power_in"))
      (node (ref "U5") (pin "7") (pinfunction "GND_7") (pintype "power_in"))
      (node (ref "U6") (pin "1") (pinfunction "GND_1") (pintype "power_in"))
      (node (ref "U6") (pin "7") (pinfunction "GND_7") (pintype "power_in"))
      (node (ref "U7") (pin "1") (pinfunction "GND_1") (pintype "power_in"))
      (node (ref "U7") (pin "7") (pinfunction "GND_7") (pintype "power_in"))
      (node (ref "U8") (pin "3") (pinfunction "GND_3") (pintype "power_in"))
      (node (ref "U9") (pin "3") (pinfunction "GND_3") (pintype "power_in"))
    )
    (net (code "22") (name "Net-(C11-Pad2)") (class "Default")
      (node (ref "C11") (pin "2") (pinfunction "2_2") (pintype "passive"))
      (node (ref "C5") (pin "1") (pinfunction "1_1") (pintype "passive"))
      (node (ref "F1") (pin "1") (pinfunction "1_1") (pintype "passive"))
      (node (ref "L2") (pin "2") (pinfunction "2_2") (pintype "passive"))
    )
    (net (code "23") (name "Net-(C13-Pad2)") (class "Default")
      (node (ref "C13") (pin "2") (pinfunction "2_2") (pintype "passive"))
      (node (ref "C7") (pin "1") (pinfunction "1_1") (pintype "passive"))
      (node (ref "F2") (pin "1") (pinfunction "1_1") (pintype "passive"))
      (node (ref "L4") (pin "2") (pinfunction "2_2") (pintype "passive"))
    )
    (net (code "24") (name "Net-(C15-Pad2)") (class "Default")
      (node (ref "C15") (pin "2") (pinfunction "2_2") (pintype "passive"))
      (node (ref "C9") (pin "1") (pinfunction "1_1") (pintype "passive"))
      (node (ref "F3") (pin "1") (pinfunction "1_1") (pintype "passive"))
      (node (ref "L6") (pin "2") (pinfunction "2_2") (pintype "passive"))
    )
    (net (code "25") (name "Net-(C23-Pad1)") (class "Default")
      (node (ref "C23") (pin "1") (pinfunction "1_1") (pintype "passive"))
      (node (ref "C27") (pin "2") (pinfunction "2_2") (pintype "passive"))
      (node (ref "F4") (pin "1") (pinfunction "1_1") (pintype "passive"))
      (node (ref "L8") (pin "2") (pinfunction "2_2") (pintype "passive"))
    )
    (net (code "26") (name "Net-(C25-Pad1)") (class "Default")
      (node (ref "C25") (pin "1") (pinfunction "1_1") (pintype "passive"))
      (node (ref "C29") (pin "2") (pinfunction "2_2") (pintype "passive"))
      (node (ref "F5") (pin "1") (pinfunction "1_1") (pintype "passive"))
      (node (ref "L10") (pin "2") (pinfunction "2_2") (pintype "passive"))
    )
    (net (code "27") (name "Net-(C32-Pad1)") (class "Default")
      (node (ref "C32") (pin "1") (pinfunction "1_1") (pintype "passive"))
      (node (ref "C34") (pin "2") (pinfunction "2_2") (pintype "passive"))
      (node (ref "F6") (pin "1") (pinfunction "1_1") (pintype "passive"))
      (node (ref "L12") (pin "2") (pinfunction "2_2") (pintype "passive"))
    )
    (net (code "28") (name "Net-(D1-A)") (class "Default")
      (node (ref "D1") (pin "1") (pinfunction "A_1") (pintype "passive"))
      (node (ref "R10") (pin "1") (pinfunction "1_1") (pintype "passive"))
    )
    (net (code "29") (name "Net-(D2-A)") (class "Default")
      (node (ref "D2") (pin "1") (pinfunction "A_1") (pintype "passive"))
      (node (ref "R11") (pin "1") (pinfunction "1_1") (pintype "passive"))
    )
    (net (code "30") (name "Net-(D8-A)") (class "Default")
      (node (ref "D8") (pin "1") (pinfunction "A_1") (pintype "passive"))
      (node (ref "R26") (pin "1") (pinfunction "1_1") (pintype "passive"))
    )
    (net (code "31") (name "Net-(D9-A)") (class "Default")
      (node (ref "D9") (pin "1") (pinfunction "A_1") (pintype "passive"))
      (node (ref "R35") (pin "1") (pinfunction "1_1") (pintype "passive"))
    )
    (net (code "32") (name "Net-(D10-A)") (class "Default")
      (node (ref "D10") (pin "1") (pinfunction "A_1") (pintype "passive"))
      (node (ref "R32") (pin "1") (pinfunction "1_1") (pintype "passive"))
    )
    (net (code "33") (name "Net-(D11-A)") (class "Default")
      (node (ref "D11") (pin "1") (pinfunction "A_1") (pintype "passive"))
      (node (ref "R33") (pin "1") (pinfunction "1_1") (pintype "passive"))
    )
    (net (code "34") (name "Net-(D12-A)") (class "Default")
      (node (ref "D12") (pin "1") (pinfunction "A_1") (pintype "passive"))
      (node (ref "R34") (pin "1") (pinfunction "1_1") (pintype "passive"))
    )
    (net (code "35") (name "Net-(D13-A)") (class "Default")
      (node (ref "D13") (pin "1") (pinfunction "A_1") (pintype "passive"))
      (node (ref "R36") (pin "1") (pinfunction "1_1") (pintype "passive"))
    )
    (net (code "36") (name "Net-(Q1-D)") (class "Default")
      (node (ref "Q1") (pin "2") (pinfunction "D_2") (pintype "passive"))
      (node (ref "U2") (pin "3") (pinfunction "~{Inhibit}_3") (pintype "power_in"))
    )
    (net (code "37") (name "Net-(Q2-D)") (class "Default")
      (node (ref "Q2") (pin "2") (pinfunction "D_2") (pintype "passive"))
      (node (ref "U3") (pin "3") (pinfunction "~{Inhibit}_3") (pintype "power_in"))
    )
    (net (code "38") (name "Net-(Q3-D)") (class "Default")
      (node (ref "Q3") (pin "2") (pinfunction "D_2") (pintype "passive"))
      (node (ref "U5") (pin "3") (pinfunction "~{Inhibit}_3") (pintype "power_in"))
    )
    (net (code "39") (name "Net-(Q4-D)") (class "Default")
      (node (ref "Q4") (pin "2") (pinfunction "D_2") (pintype "passive"))
      (node (ref "U6") (pin "3") (pinfunction "~{Inhibit}_3") (pintype "power_in"))
    )
    (net (code "40") (name "Net-(Q5-D)") (class "Default")
      (node (ref "Q5") (pin "2") (pinfunction "D_2") (pintype "passive"))
      (node (ref "U7") (pin "3") (pinfunction "~{Inhibit}_3") (pintype "power_in"))
    )
    (net (code "41") (name "Net-(R1-+)") (class "Default")
      (node (ref "R1") (pin "3") (pinfunction "+_3") (pintype "passive"))
      (node (ref "U1") (pin "4") (pinfunction "Adjust_4") (pintype "power_in"))
    )
    (net (code "42") (name "Net-(R1--)") (class "Default")
      (node (ref "R1") (pin "1") (pinfunction "-_1") (pintype "passive"))
      (node (ref "R1") (pin "2") (pinfunction "W_2") (pintype "passive"))
      (node (ref "R2") (pin "1") (pinfunction "-_1") (pintype "passive"))
    )
    (net (code "43") (name "Net-(R2-+)") (class "Default")
      (node (ref "R2") (pin "2") (pinfunction "W_2") (pintype "passive"))
      (node (ref "R2") (pin "3") (pinfunction "+_3") (pintype "passive"))
      (node (ref "R7") (pin "2") (pinfunction "2_2") (pintype "passive"))
    )
    (net (code "44") (name "Net-(R3-+)") (class "Default")
      (node (ref "R3") (pin "3") (pinfunction "+_3") (pintype "passive"))
      (node (ref "U2") (pin "4") (pinfunction "Adjust_4") (pintype "power_in"))
    )
    (net (code "45") (name "Net-(R3--)") (class "Default")
      (node (ref "R3") (pin "1") (pinfunction "-_1") (pintype "passive"))
      (node (ref "R3") (pin "2") (pinfunction "W_2") (pintype "passive"))
      (node (ref "R4") (pin "1") (pinfunction "-_1") (pintype "passive"))
    )
    (net (code "46") (name "Net-(R4-+)") (class "Default")
      (node (ref "R4") (pin "2") (pinfunction "W_2") (pintype "passive"))
      (node (ref "R4") (pin "3") (pinfunction "+_3") (pintype "passive"))
      (node (ref "R8") (pin "2") (pinfunction "2_2") (pintype "passive"))
    )
    (net (code "47") (name "Net-(R5-+)") (class "Default")
      (node (ref "R5") (pin "3") (pinfunction "+_3") (pintype "passive"))
      (node (ref "U3") (pin "4") (pinfunction "Adjust_4") (pintype "power_in"))
    )
    (net (code "48") (name "Net-(R5--)") (class "Default")
      (node (ref "R5") (pin "1") (pinfunction "-_1") (pintype "passive"))
      (node (ref "R5") (pin "2") (pinfunction "W_2") (pintype "passive"))
      (node (ref "R6") (pin "1") (pinfunction "-_1") (pintype "passive"))
    )
    (net (code "49") (name "Net-(R6-+)") (class "Default")
      (node (ref "R6") (pin "2") (pinfunction "W_2") (pintype "passive"))
      (node (ref "R6") (pin "3") (pinfunction "+_3") (pintype "passive"))
      (node (ref "R9") (pin "2") (pinfunction "2_2") (pintype "passive"))
    )
    (net (code "50") (name "Net-(R12-+)") (class "Default")
      (node (ref "R12") (pin "3") (pinfunction "+_3") (pintype "passive"))
      (node (ref "U5") (pin "4") (pinfunction "Adjust_4") (pintype "power_in"))
    )
    (net (code "51") (name "Net-(R12--)") (class "Default")
      (node (ref "R12") (pin "1") (pinfunction "-_1") (pintype "passive"))
      (node (ref "R12") (pin "2") (pinfunction "W_2") (pintype "passive"))
      (node (ref "R13") (pin "1") (pinfunction "-_1") (pintype "passive"))
    )
    (net (code "52") (name "Net-(R13-+)") (class "Default")
      (node (ref "R13") (pin "2") (pinfunction "W_2") (pintype "passive"))
      (node (ref "R13") (pin "3") (pinfunction "+_3") (pintype "passive"))
      (node (ref "R16") (pin "2") (pinfunction "2_2") (pintype "passive"))
    )
    (net (code "53") (name "Net-(R14-+)") (class "Default")
      (node (ref "R14") (pin "3") (pinfunction "+_3") (pintype "passive"))
      (node (ref "U6") (pin "4") (pinfunction "Adjust_4") (pintype "power_in"))
    )
    (net (code "54") (name "Net-(R14--)") (class "Default")
      (node (ref "R14") (pin "1") (pinfunction "-_1") (pintype "passive"))
      (node (ref "R14") (pin "2") (pinfunction "W_2") (pintype "passive"))
      (node (ref "R15") (pin "1") (pinfunction "-_1") (pintype "passive"))
    )
    (net (code "55") (name "Net-(R15-+)") (class "Default")
      (node (ref "R15") (pin "2") (pinfunction "W_2") (pintype "passive"))
      (node (ref "R15") (pin "3") (pinfunction "+_3") (pintype "passive"))
      (node (ref "R17") (pin "2") (pinfunction "2_2") (pintype "passive"))
    )
    (net (code "56") (name "Net-(R24-+)") (class "Default")
      (node (ref "R24") (pin "3") (pinfunction "+_3") (pintype "passive"))
      (node (ref "U7") (pin "4") (pinfunction "Adjust_4") (pintype "power_in"))
    )
    (net (code "57") (name "Net-(R24--)") (class "Default")
      (node (ref "R24") (pin "1") (pinfunction "-_1") (pintype "passive"))
      (node (ref "R24") (pin "2") (pinfunction "W_2") (pintype "passive"))
      (node (ref "R25") (pin "1") (pinfunction "-_1") (pintype "passive"))
    )
    (net (code "58") (name "Net-(R25-+)") (class "Default")
      (node (ref "R25") (pin "2") (pinfunction "W_2") (pintype "passive"))
      (node (ref "R25") (pin "3") (pinfunction "+_3") (pintype "passive"))
      (node (ref "R27") (pin "2") (pinfunction "2_2") (pintype "passive"))
    )
    (net (code "59") (name "Net-(U1-Sense)") (class "Default")
      (node (ref "C4") (pin "1") (pinfunction "1_1") (pintype "passive"))
      (node (ref "L2") (pin "1") (pinfunction "1_1") (pintype "passive"))
      (node (ref "U1") (pin "5") (pinfunction "Sense_5") (pintype "power_in"))
      (node (ref "U1") (pin "6") (pinfunction "VO_6") (pintype "power_in"))
    )
    (net (code "60") (name "Net-(U1-VI)") (class "Default")
      (node (ref "C10") (pin "2") (pinfunction "2_2") (pintype "passive"))
      (node (ref "L1") (pin "2") (pinfunction "2_2") (pintype "passive"))
      (node (ref "U1") (pin "2") (pinfunction "VI_2") (pintype "power_in"))
    )
    (net (code "61") (name "Net-(U2-Sense)") (class "Default")
      (node (ref "C6") (pin "1") (pinfunction "1_1") (pintype "passive"))
      (node (ref "L4") (pin "1") (pinfunction "1_1") (pintype "passive"))
      (node (ref "U2") (pin "5") (pinfunction "Sense_5") (pintype "power_in"))
      (node (ref "U2") (pin "6") (pinfunction "VO_6") (pintype "power_in"))
    )
    (net (code "62") (name "Net-(U2-VI)") (class "Default")
      (node (ref "C12") (pin "2") (pinfunction "2_2") (pintype "passive"))
      (node (ref "L3") (pin "2") (pinfunction "2_2") (pintype "passive"))
      (node (ref "U2") (pin "2") (pinfunction "VI_2") (pintype "power_in"))
    )
    (net (code "63") (name "Net-(U3-Sense)") (class "Default")
      (node (ref "C8") (pin "1") (pinfunction "1_1") (pintype "passive"))
      (node (ref "L6") (pin "1") (pinfunction "1_1") (pintype "passive"))
      (node (ref "U3") (pin "5") (pinfunction "Sense_5") (pintype "power_in"))
      (node (ref "U3") (pin "6") (pinfunction "VO_6") (pintype "power_in"))
    )
    (net (code "64") (name "Net-(U3-VI)") (class "Default")
      (node (ref "C14") (pin "2") (pinfunction "2_2") (pintype "passive"))
      (node (ref "L5") (pin "2") (pinfunction "2_2") (pintype "passive"))
      (node (ref "U3") (pin "2") (pinfunction "VI_2") (pintype "power_in"))
    )
    (net (code "65") (name "Net-(U5-Sense)") (class "Default")
      (node (ref "C22") (pin "1") (pinfunction "1_1") (pintype "passive"))
      (node (ref "L8") (pin "1") (pinfunction "1_1") (pintype "passive"))
      (node (ref "U5") (pin "5") (pinfunction "Sense_5") (pintype "power_in"))
      (node (ref "U5") (pin "6") (pinfunction "VO_6") (pintype "power_in"))
    )
    (net (code "66") (name "Net-(U5-VI)") (class "Default")
      (node (ref "C26") (pin "2") (pinfunction "2_2") (pintype "passive"))
      (node (ref "L7") (pin "2") (pinfunction "2_2") (pintype "passive"))
      (node (ref "U5") (pin "2") (pinfunction "VI_2") (pintype "power_in"))
    )
    (net (code "67") (name "Net-(U6-Sense)") (class "Default")
      (node (ref "C24") (pin "1") (pinfunction "1_1") (pintype "passive"))
      (node (ref "L10") (pin "1") (pinfunction "1_1") (pintype "passive"))
      (node (ref "U6") (pin "5") (pinfunction "Sense_5") (pintype "power_in"))
      (node (ref "U6") (pin "6") (pinfunction "VO_6") (pintype "power_in"))
    )
    (net (code "68") (name "Net-(U6-VI)") (class "Default")
      (node (ref "C28") (pin "2") (pinfunction "2_2") (pintype "passive"))
      (node (ref "L9") (pin "2") (pinfunction "2_2") (pintype "passive"))
      (node (ref "U6") (pin "2") (pinfunction "VI_2") (pintype "power_in"))
    )
    (net (code "69") (name "Net-(U7-Sense)") (class "Default")
      (node (ref "C31") (pin "1") (pinfunction "1_1") (pintype "passive"))
      (node (ref "L12") (pin "1") (pinfunction "1_1") (pintype "passive"))
      (node (ref "U7") (pin "5") (pinfunction "Sense_5") (pintype "power_in"))
      (node (ref "U7") (pin "6") (pinfunction "VO_6") (pintype "power_in"))
    )
    (net (code "70") (name "Net-(U7-VI)") (class "Default")
      (node (ref "C33") (pin "2") (pinfunction "2_2") (pintype "passive"))
      (node (ref "L11") (pin "2") (pinfunction "2_2") (pintype "passive"))
      (node (ref "U7") (pin "2") (pinfunction "VI_2") (pintype "power_in"))
    )
    (net (code "71") (name "Net-(U10-AN0{slash}VREF+{slash}CN2{slash}RA0)") (class "Default")
      (node (ref "R29") (pin "1") (pinfunction "1_1") (pintype "passive"))
      (node (ref "R30") (pin "2") (pinfunction "2_2") (pintype "passive"))
      (node (ref "U10") (pin "19") (pinfunction "AN0/VREF+/CN2/RA0_19") (pintype "bidirectional"))
    )
    (net (code "72") (name "Net-(U10-OSCI{slash}CLKI{slash}CN30{slash}RA2)") (class "Default")
      (node (ref "C37") (pin "2") (pinfunction "2_2") (pintype "passive"))
      (node (ref "U10") (pin "30") (pinfunction "OSCI/CLKI/CN30/RA2_30") (pintype "input"))
      (node (ref "Y1") (pin "1") (pinfunction "OSC1_1") (pintype "passive"))
    )
    (net (code "73") (name "Net-(U10-OSCO{slash}CLKO{slash}CN29{slash}RA3)") (class "Default")
      (node (ref "C39") (pin "2") (pinfunction "2_2") (pintype "passive"))
      (node (ref "U10") (pin "31") (pinfunction "OSCO/CLKO/CN29/RA3_31") (pintype "bidirectional"))
      (node (ref "Y1") (pin "2") (pinfunction "OSC2_2") (pintype "passive"))
    )
    (net (code "74") (name "Net-(U10-PWM2H1{slash}RP22{slash}CN18{slash}PMA1{slash}RC6)") (class "Default")
      (node (ref "U10") (pin "2") (pinfunction "PWM2H1/RP22/CN18/PMA1/RC6_2") (pintype "bidirectional"))
      (node (ref "U8") (pin "2") (pinfunction "A_2") (pintype "input"))
    )
    (net (code "75") (name "Net-(U10-PWM2L1{slash}RP23{slash}CN17{slash}PMA0{slash}RC7)") (class "Default")
      (node (ref "U10") (pin "3") (pinfunction "PWM2L1/RP23/CN17/PMA0/RC7_3") (pintype "bidirectional"))
      (node (ref "U9") (pin "2") (pinfunction "A_2") (pintype "input"))
    )
    (net (code "76") (name "Net-(U10-RP24{slash}CN20{slash}PMA5{slash}RC8)") (class "Default")
      (node (ref "U10") (pin "4") (pinfunction "RP24/CN20/PMA5/RC8_4") (pintype "bidirectional"))
      (node (ref "U11") (pin "2") (pinfunction "A_2") (pintype "input"))
    )
    (net (code "77") (name "Net-(U10-RP25{slash}CN19{slash}PMA6{slash}RC9)") (class "Default")
      (node (ref "U10") (pin "5") (pinfunction "RP25/CN19/PMA6/RC9_5") (pintype "bidirectional"))
      (node (ref "U13") (pin "2") (pinfunction "A_2") (pintype "input"))
    )
    (net (code "78") (name "Net-(U10-SDA1{slash}RP9{slash}CN21{slash}PMD3{slash}RB9)") (class "Default")
      (node (ref "U10") (pin "1") (pinfunction "SDA1/RP9/CN21/PMD3/RB9_1") (pintype "bidirectional"))
      (node (ref "U12") (pin "2") (pinfunction "A_2") (pintype "input"))
    )
    (net (code "79") (name "Net-(U10-TCK{slash}PMA7{slash}RA7)") (class "Default")
      (node (ref "R40") (pin "2") (pinfunction "2_2") (pintype "passive"))
      (node (ref "S2") (pin "8") (pinfunction "8_8") (pintype "passive"))
      (node (ref "U10") (pin "13") (pinfunction "TCK/PMA7/RA7_13") (pintype "bidirectional"))
    )
    (net (code "80") (name "Net-(U10-TDI{slash}PMA9{slash}RA9)") (class "Default")
      (node (ref "R38") (pin "2") (pinfunction "2_2") (pintype "passive"))
      (node (ref "S2") (pin "6") (pinfunction "6_6") (pintype "passive"))
      (node (ref "U10") (pin "35") (pinfunction "TDI/PMA9/RA9_35") (pintype "bidirectional"))
    )
    (net (code "81") (name "Net-(U10-TDO{slash}PMA8{slash}RA8)") (class "Default")
      (node (ref "R39") (pin "2") (pinfunction "2_2") (pintype "passive"))
      (node (ref "S2") (pin "7") (pinfunction "7_7") (pintype "passive"))
      (node (ref "U10") (pin "32") (pinfunction "TDO/PMA8/RA8_32") (pintype "bidirectional"))
    )
    (net (code "82") (name "Net-(U10-TMS{slash}PMA10{slash}RA10)") (class "Default")
      (node (ref "R37") (pin "2") (pinfunction "2_2") (pintype "passive"))
      (node (ref "S2") (pin "5") (pinfunction "5_5") (pintype "passive"))
      (node (ref "U10") (pin "12") (pinfunction "TMS/PMA10/RA10_12") (pintype "bidirectional"))
    )
    (net (code "83") (name "Net-(U10-VCAP{slash}VDDCORE)") (class "Default")
      (node (ref "C40") (pin "1") (pinfunction "1_1") (pintype "passive"))
      (node (ref "U10") (pin "7") (pinfunction "VCAP/VDDCORE_7") (pintype "power_in"))
    )
    (net (code "84") (name "Net-(U14-RS)") (class "Default")
      (node (ref "R31") (pin "2") (pinfunction "2_2") (pintype "passive"))
      (node (ref "U14") (pin "8") (pinfunction "RS_8") (pintype "passive"))
    )
    (net (code "85") (name "VBAT") (class "Default")
      (node (ref "C1") (pin "2") (pinfunction "2_2") (pintype "passive"))
      (node (ref "L1") (pin "1") (pinfunction "1_1") (pintype "passive"))
      (node (ref "P4") (pin "2") (pinfunction "2_2") (pintype "passive"))
      (node (ref "R26") (pin "2") (pinfunction "2_2") (pintype "passive"))
      (node (ref "R29") (pin "2") (pinfunction "2_2") (pintype "passive"))
    )
    (net (code "86") (name "VBAT2") (class "Default")
      (node (ref "C2") (pin "2") (pinfunction "2_2") (pintype "passive"))
      (node (ref "C20") (pin "2") (pinfunction "2_2") (pintype "passive"))
      (node (ref "C21") (pin "2") (pinfunction "2_2") (pintype "passive"))
      (node (ref "C3") (pin "2") (pinfunction "2_2") (pintype "passive"))
      (node (ref "C30") (pin "2") (pinfunction "2_2") (pintype "passive"))
      (node (ref "L11") (pin "1") (pinfunction "1_1") (pintype "passive"))
      (node (ref "L3") (pin "1") (pinfunction "1_1") (pintype "passive"))
      (node (ref "L5") (pin "1") (pinfunction "1_1") (pintype "passive"))
      (node (ref "L7") (pin "1") (pinfunction "1_1") (pintype "passive"))
      (node (ref "L9") (pin "1") (pinfunction "1_1") (pintype "passive"))
      (node (ref "P6") (pin "2") (pinfunction "2_2") (pintype "passive"))
    )
    (net (code "87") (name "VCC") (class "Default")
      (node (ref "C16") (pin "1") (pinfunction "1_1") (pintype "passive"))
      (node (ref "C18") (pin "2") (pinfunction "2_2") (pintype "passive"))
      (node (ref "C38") (pin "2") (pinfunction "2_2") (pintype "passive"))
      (node (ref "F1") (pin "2") (pinfunction "2_2") (pintype "passive"))
      (node (ref "P2") (pin "1") (pinfunction "1_1") (pintype "passive"))
      (node (ref "R10") (pin "2") (pinfunction "2_2") (pintype "passive"))
      (node (ref "U11") (pin "5") (pinfunction "VCC_5") (pintype "power_in"))
      (node (ref "U12") (pin "5") (pinfunction "VCC_5") (pintype "power_in"))
      (node (ref "U13") (pin "5") (pinfunction "VCC_5") (pintype "power_in"))
      (node (ref "U14") (pin "3") (pinfunction "VDD_3") (pintype "power_in"))
      (node (ref "U4") (pin "1") (pinfunction "IN_1") (pintype "power_in"))
      (node (ref "U8") (pin "5") (pinfunction "VCC_5") (pintype "power_in"))
      (node (ref "U9") (pin "5") (pinfunction "VCC_5") (pintype "power_in"))
    )
    (net (code "88") (name "VDD1") (class "Default")
      (node (ref "F2") (pin "2") (pinfunction "2_2") (pintype "passive"))
      (node (ref "P2") (pin "7") (pinfunction "7_7") (pintype "passive"))
      (node (ref "P2") (pin "9") (pinfunction "9_9") (pintype "passive"))
      (node (ref "R18") (pin "2") (pinfunction "2_2") (pintype "passive"))
      (node (ref "R32") (pin "2") (pinfunction "2_2") (pintype "passive"))
    )
    (net (code "89") (name "VDD2") (class "Default")
      (node (ref "F3") (pin "2") (pinfunction "2_2") (pintype "passive"))
      (node (ref "P2") (pin "11") (pinfunction "11_11") (pintype "passive"))
      (node (ref "P2") (pin "13") (pinfunction "13_13") (pintype "passive"))
      (node (ref "R19") (pin "2") (pinfunction "2_2") (pintype "passive"))
      (node (ref "R33") (pin "2") (pinfunction "2_2") (pintype "passive"))
    )
    (net (code "90") (name "VDD3") (class "Default")
      (node (ref "F4") (pin "2") (pinfunction "2_2") (pintype "passive"))
      (node (ref "P1") (pin "15") (pinfunction "15_15") (pintype "passive"))
      (node (ref "P1") (pin "17") (pinfunction "17_17") (pintype "passive"))
      (node (ref "R20") (pin "2") (pinfunction "2_2") (pintype "passive"))
      (node (ref "R34") (pin "2") (pinfunction "2_2") (pintype "passive"))
    )
    (net (code "91") (name "VDD4") (class "Default")
      (node (ref "F5") (pin "2") (pinfunction "2_2") (pintype "passive"))
      (node (ref "P2") (pin "19") (pinfunction "19_19") (pintype "passive"))
      (node (ref "P2") (pin "21") (pinfunction "21_21") (pintype "passive"))
      (node (ref "R21") (pin "2") (pinfunction "2_2") (pintype "passive"))
      (node (ref "R35") (pin "2") (pinfunction "2_2") (pintype "passive"))
    )
    (net (code "92") (name "VDD5") (class "Default")
      (node (ref "F6") (pin "2") (pinfunction "2_2") (pintype "passive"))
      (node (ref "P2") (pin "23") (pinfunction "23_23") (pintype "passive"))
      (node (ref "P2") (pin "25") (pinfunction "25_25") (pintype "passive"))
      (node (ref "R22") (pin "2") (pinfunction "2_2") (pintype "passive"))
      (node (ref "R36") (pin "2") (pinfunction "2_2") (pintype "passive"))
    )
    (net (code "93") (name "unconnected-(P1-Pad1)") (class "Default")
      (node (ref "P1") (pin "1") (pinfunction "1_1") (pintype "passive+no_connect"))
    )
    (net (code "94") (name "unconnected-(P1-Pad2)") (class "Default")
      (node (ref "P1") (pin "2") (pinfunction "2_2") (pintype "passive+no_connect"))
    )
    (net (code "95") (name "unconnected-(P1-Pad3)") (class "Default")
      (node (ref "P1") (pin "3") (pinfunction "3_3") (pintype "passive+no_connect"))
    )
    (net (code "96") (name "unconnected-(P1-Pad4)") (class "Default")
      (node (ref "P1") (pin "4") (pinfunction "4_4") (pintype "passive+no_connect"))
    )
    (net (code "97") (name "unconnected-(P1-Pad5)") (class "Default")
      (node (ref "P1") (pin "5") (pinfunction "5_5") (pintype "passive+no_connect"))
    )
    (net (code "98") (name "unconnected-(P1-Pad6)") (class "Default")
      (node (ref "P1") (pin "6") (pinfunction "6_6") (pintype "passive+no_connect"))
    )
    (net (code "99") (name "unconnected-(P1-Pad7)") (class "Default")
      (node (ref "P1") (pin "7") (pinfunction "7_7") (pintype "passive+no_connect"))
    )
    (net (code "100") (name "unconnected-(P1-Pad8)") (class "Default")
      (node (ref "P1") (pin "8") (pinfunction "8_8") (pintype "passive"))
    )
    (net (code "101") (name "unconnected-(P1-Pad9)") (class "Default")
      (node (ref "P1") (pin "9") (pinfunction "9_9") (pintype "passive+no_connect"))
    )
    (net (code "102") (name "unconnected-(P1-Pad11)") (class "Default")
      (node (ref "P1") (pin "11") (pinfunction "11_11") (pintype "passive+no_connect"))
    )
    (net (code "103") (name "unconnected-(P1-Pad13)") (class "Default")
      (node (ref "P1") (pin "13") (pinfunction "13_13") (pintype "passive+no_connect"))
    )
    (net (code "104") (name "unconnected-(P1-Pad19)") (class "Default")
      (node (ref "P1") (pin "19") (pinfunction "19_19") (pintype "passive+no_connect"))
    )
    (net (code "105") (name "unconnected-(P1-Pad21)") (class "Default")
      (node (ref "P1") (pin "21") (pinfunction "21_21") (pintype "passive+no_connect"))
    )
    (net (code "106") (name "unconnected-(P1-Pad23)") (class "Default")
      (node (ref "P1") (pin "23") (pinfunction "23_23") (pintype "passive+no_connect"))
    )
    (net (code "107") (name "unconnected-(P1-Pad25)") (class "Default")
      (node (ref "P1") (pin "25") (pinfunction "25_25") (pintype "passive+no_connect"))
    )
    (net (code "108") (name "unconnected-(P2-Pad15)") (class "Default")
      (node (ref "P2") (pin "15") (pinfunction "15_15") (pintype "passive+no_connect"))
    )
    (net (code "109") (name "unconnected-(P2-Pad17)") (class "Default")
      (node (ref "P2") (pin "17") (pinfunction "17_17") (pintype "passive+no_connect"))
    )
    (net (code "110") (name "unconnected-(U1-~{Inhibit}-Pad3)") (class "Default")
      (node (ref "U1") (pin "3") (pinfunction "~{Inhibit}_3") (pintype "power_in+no_connect"))
    )
    (net (code "111") (name "unconnected-(U10-AN1{slash}VREF-{slash}CN3{slash}RA1-Pad20)") (class "Default")
      (node (ref "U10") (pin "20") (pinfunction "AN1/VREF-/CN3/RA1_20") (pintype "bidirectional+no_connect"))
    )
    (net (code "112") (name "unconnected-(U10-AN6{slash}DAC1RM{slash}RP16{slash}CN8{slash}RC0-Pad25)") (class "Default")
      (node (ref "U10") (pin "25") (pinfunction "AN6/DAC1RM/RP16/CN8/RC0_25") (pintype "bidirectional+no_connect"))
    )
    (net (code "113") (name "unconnected-(U10-AN7{slash}DAC1LM{slash}RP17{slash}CN9{slash}RC1-Pad26)") (class "Default")
      (node (ref "U10") (pin "26") (pinfunction "AN7/DAC1LM/RP17/CN9/RC1_26") (pintype "bidirectional+no_connect"))
    )
    (net (code "114") (name "unconnected-(U10-AN8{slash}CVREF{slash}RP18{slash}PMA2{slash}CN10{slash}RC2-Pad27)") (class "Default")
      (node (ref "U10") (pin "27") (pinfunction "AN8/CVREF/RP18/PMA2/CN10/RC2_27") (pintype "bidirectional+no_connect"))
    )
    (net (code "115") (name "unconnected-(U10-PGD3{slash}EMUD3{slash}ASDA1{slash}RP5{slash}CN27{slash}PMD7{slash}RB5-Pad41)") (class "Default")
      (node (ref "U10") (pin "41") (pinfunction "PGD3/EMUD3/ASDA1/RP5/CN27/PMD7/RB5_41") (pintype "bidirectional+no_connect"))
    )
    (net (code "116") (name "unconnected-(U10-PWM1H1{slash}DAC1LP{slash}RTCC{slash}RP14{slash}CN12{slash}PMWR{slash}RB14-Pad14)") (class "Default")
      (node (ref "U10") (pin "14") (pinfunction "PWM1H1/DAC1LP/RTCC/RP14/CN12/PMWR/RB14_14") (pintype "bidirectional+no_connect"))
    )
    (net (code "117") (name "unconnected-(U10-PWM1H2{slash}DAC1RP{slash}RP12{slash}CN14{slash}PMD0{slash}RB12-Pad10)") (class "Default")
      (node (ref "U10") (pin "10") (pinfunction "PWM1H2/DAC1RP/RP12/CN14/PMD0/RB12_10") (pintype "bidirectional+no_connect"))
    )
    (net (code "118") (name "unconnected-(U10-PWM1L2{slash}DAC1RN{slash}RP13{slash}CN13{slash}PMRD{slash}RB13-Pad11)") (class "Default")
      (node (ref "U10") (pin "11") (pinfunction "PWM1L2/DAC1RN/RP13/CN13/PMRD/RB13_11") (pintype "bidirectional+no_connect"))
    )
    (net (code "119") (name "unconnected-(U10-RP19{slash}CN28{slash}PMBE{slash}RC3-Pad36)") (class "Default")
      (node (ref "U10") (pin "36") (pinfunction "RP19/CN28/PMBE/RC3_36") (pintype "bidirectional+no_connect"))
    )
    (net (code "120") (name "unconnected-(U10-RP20{slash}CN25{slash}PMA4{slash}RC4-Pad37)") (class "Default")
      (node (ref "U10") (pin "37") (pinfunction "RP20/CN25/PMA4/RC4_37") (pintype "bidirectional+no_connect"))
    )
    (net (code "121") (name "unconnected-(U10-RP21{slash}CN26{slash}PMA3{slash}RC5-Pad38)") (class "Default")
      (node (ref "U10") (pin "38") (pinfunction "RP21/CN26/PMA3/RC5_38") (pintype "bidirectional"))
    )
    (net (code "122") (name "unconnected-(U10-SCL1{slash}RP8{slash}CN22{slash}PMD4{slash}RB8-Pad44)") (class "Default")
      (node (ref "U10") (pin "44") (pinfunction "SCL1/RP8/CN22/PMD4/RB8_44") (pintype "bidirectional+no_connect"))
    )
    (net (code "123") (name "unconnected-(U14-VREF-Pad5)") (class "Default")
      (node (ref "U14") (pin "5") (pinfunction "VREF_5") (pintype "output+no_connect"))
    )
  )
)
